# ascender_board.net
KiCad netlist of a schematic drawn in EAGLE
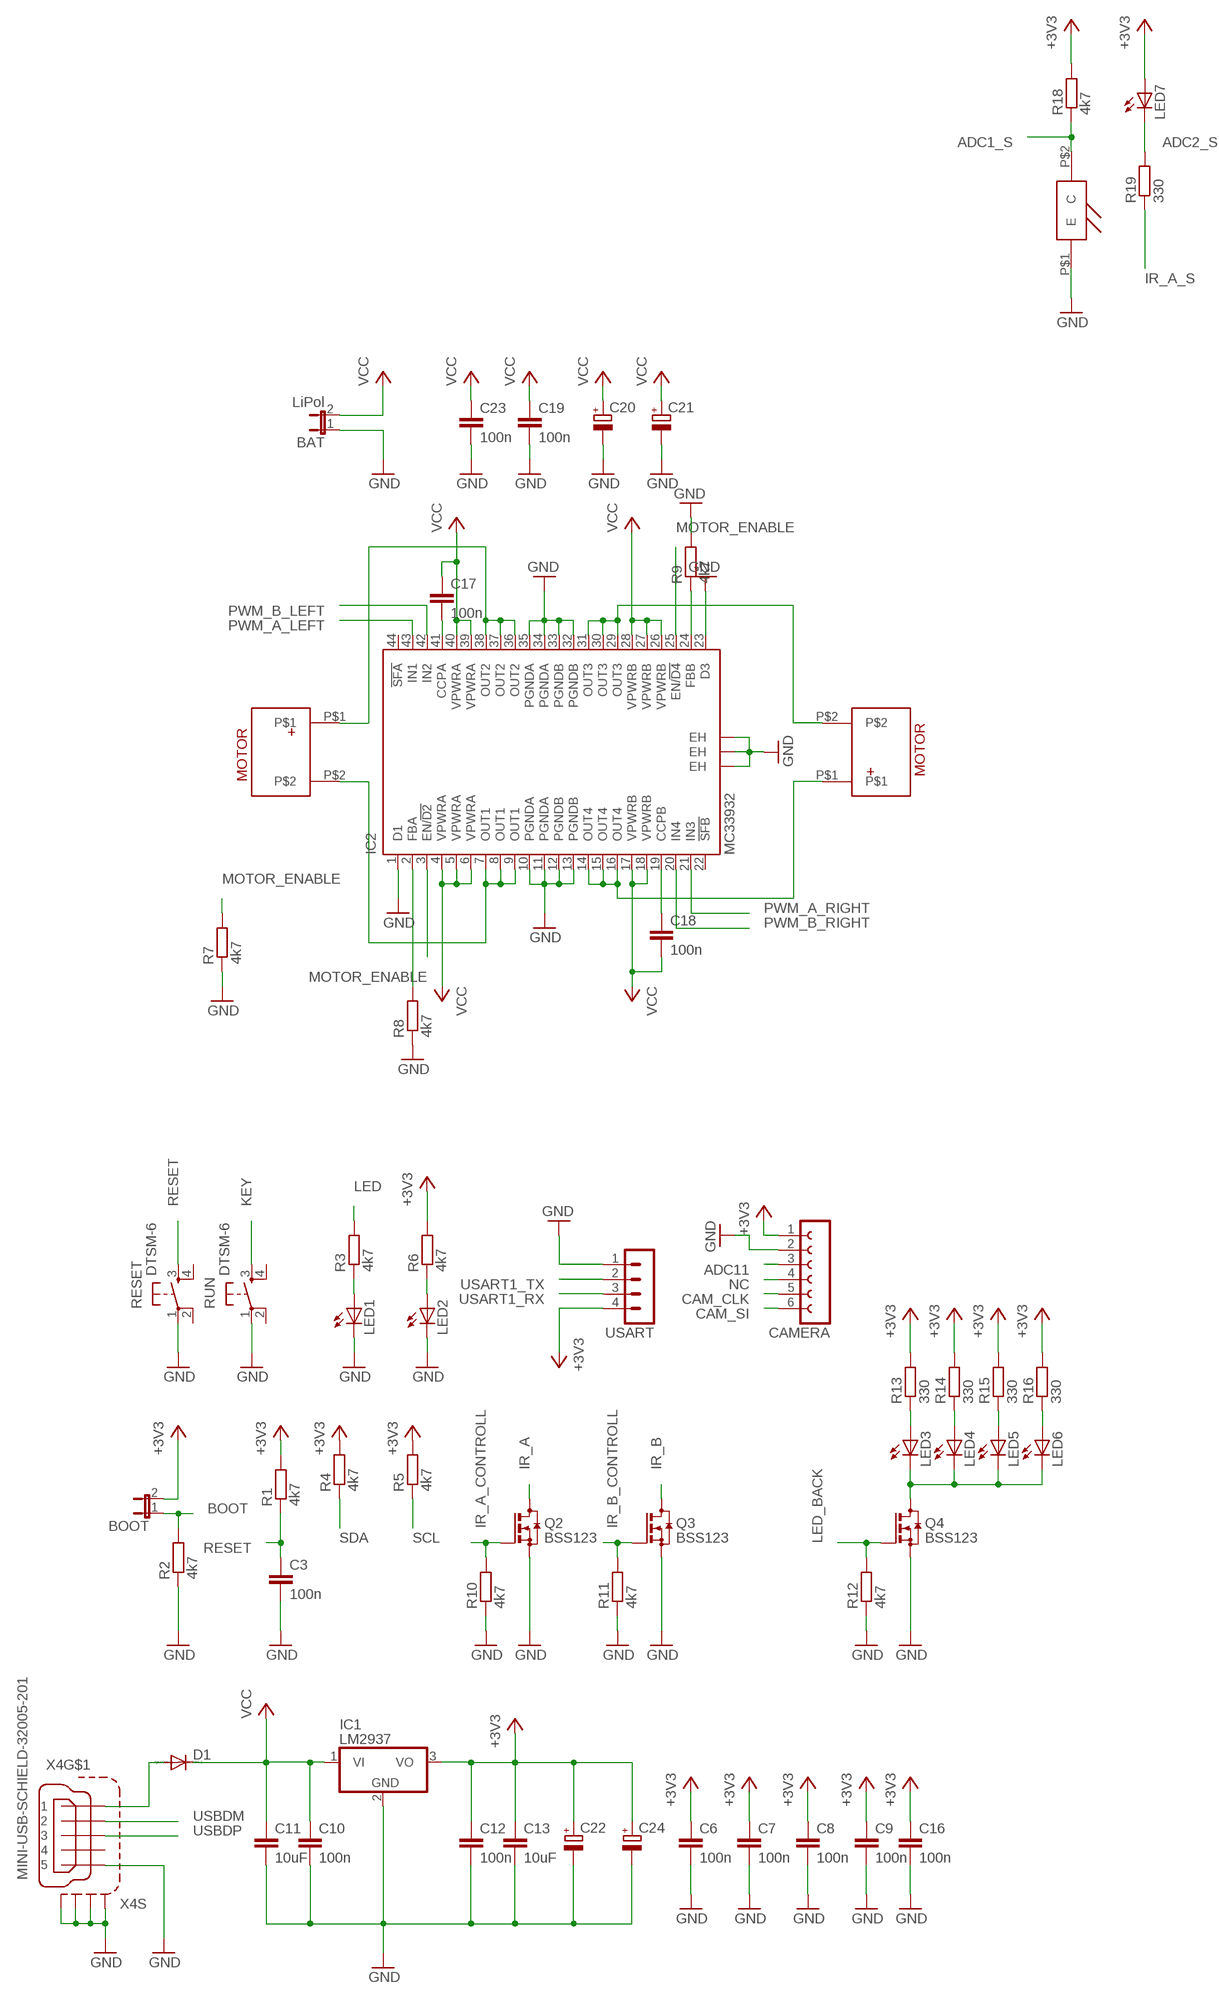
[diagram p0: schematic, sheet 1, part 1 of 2]
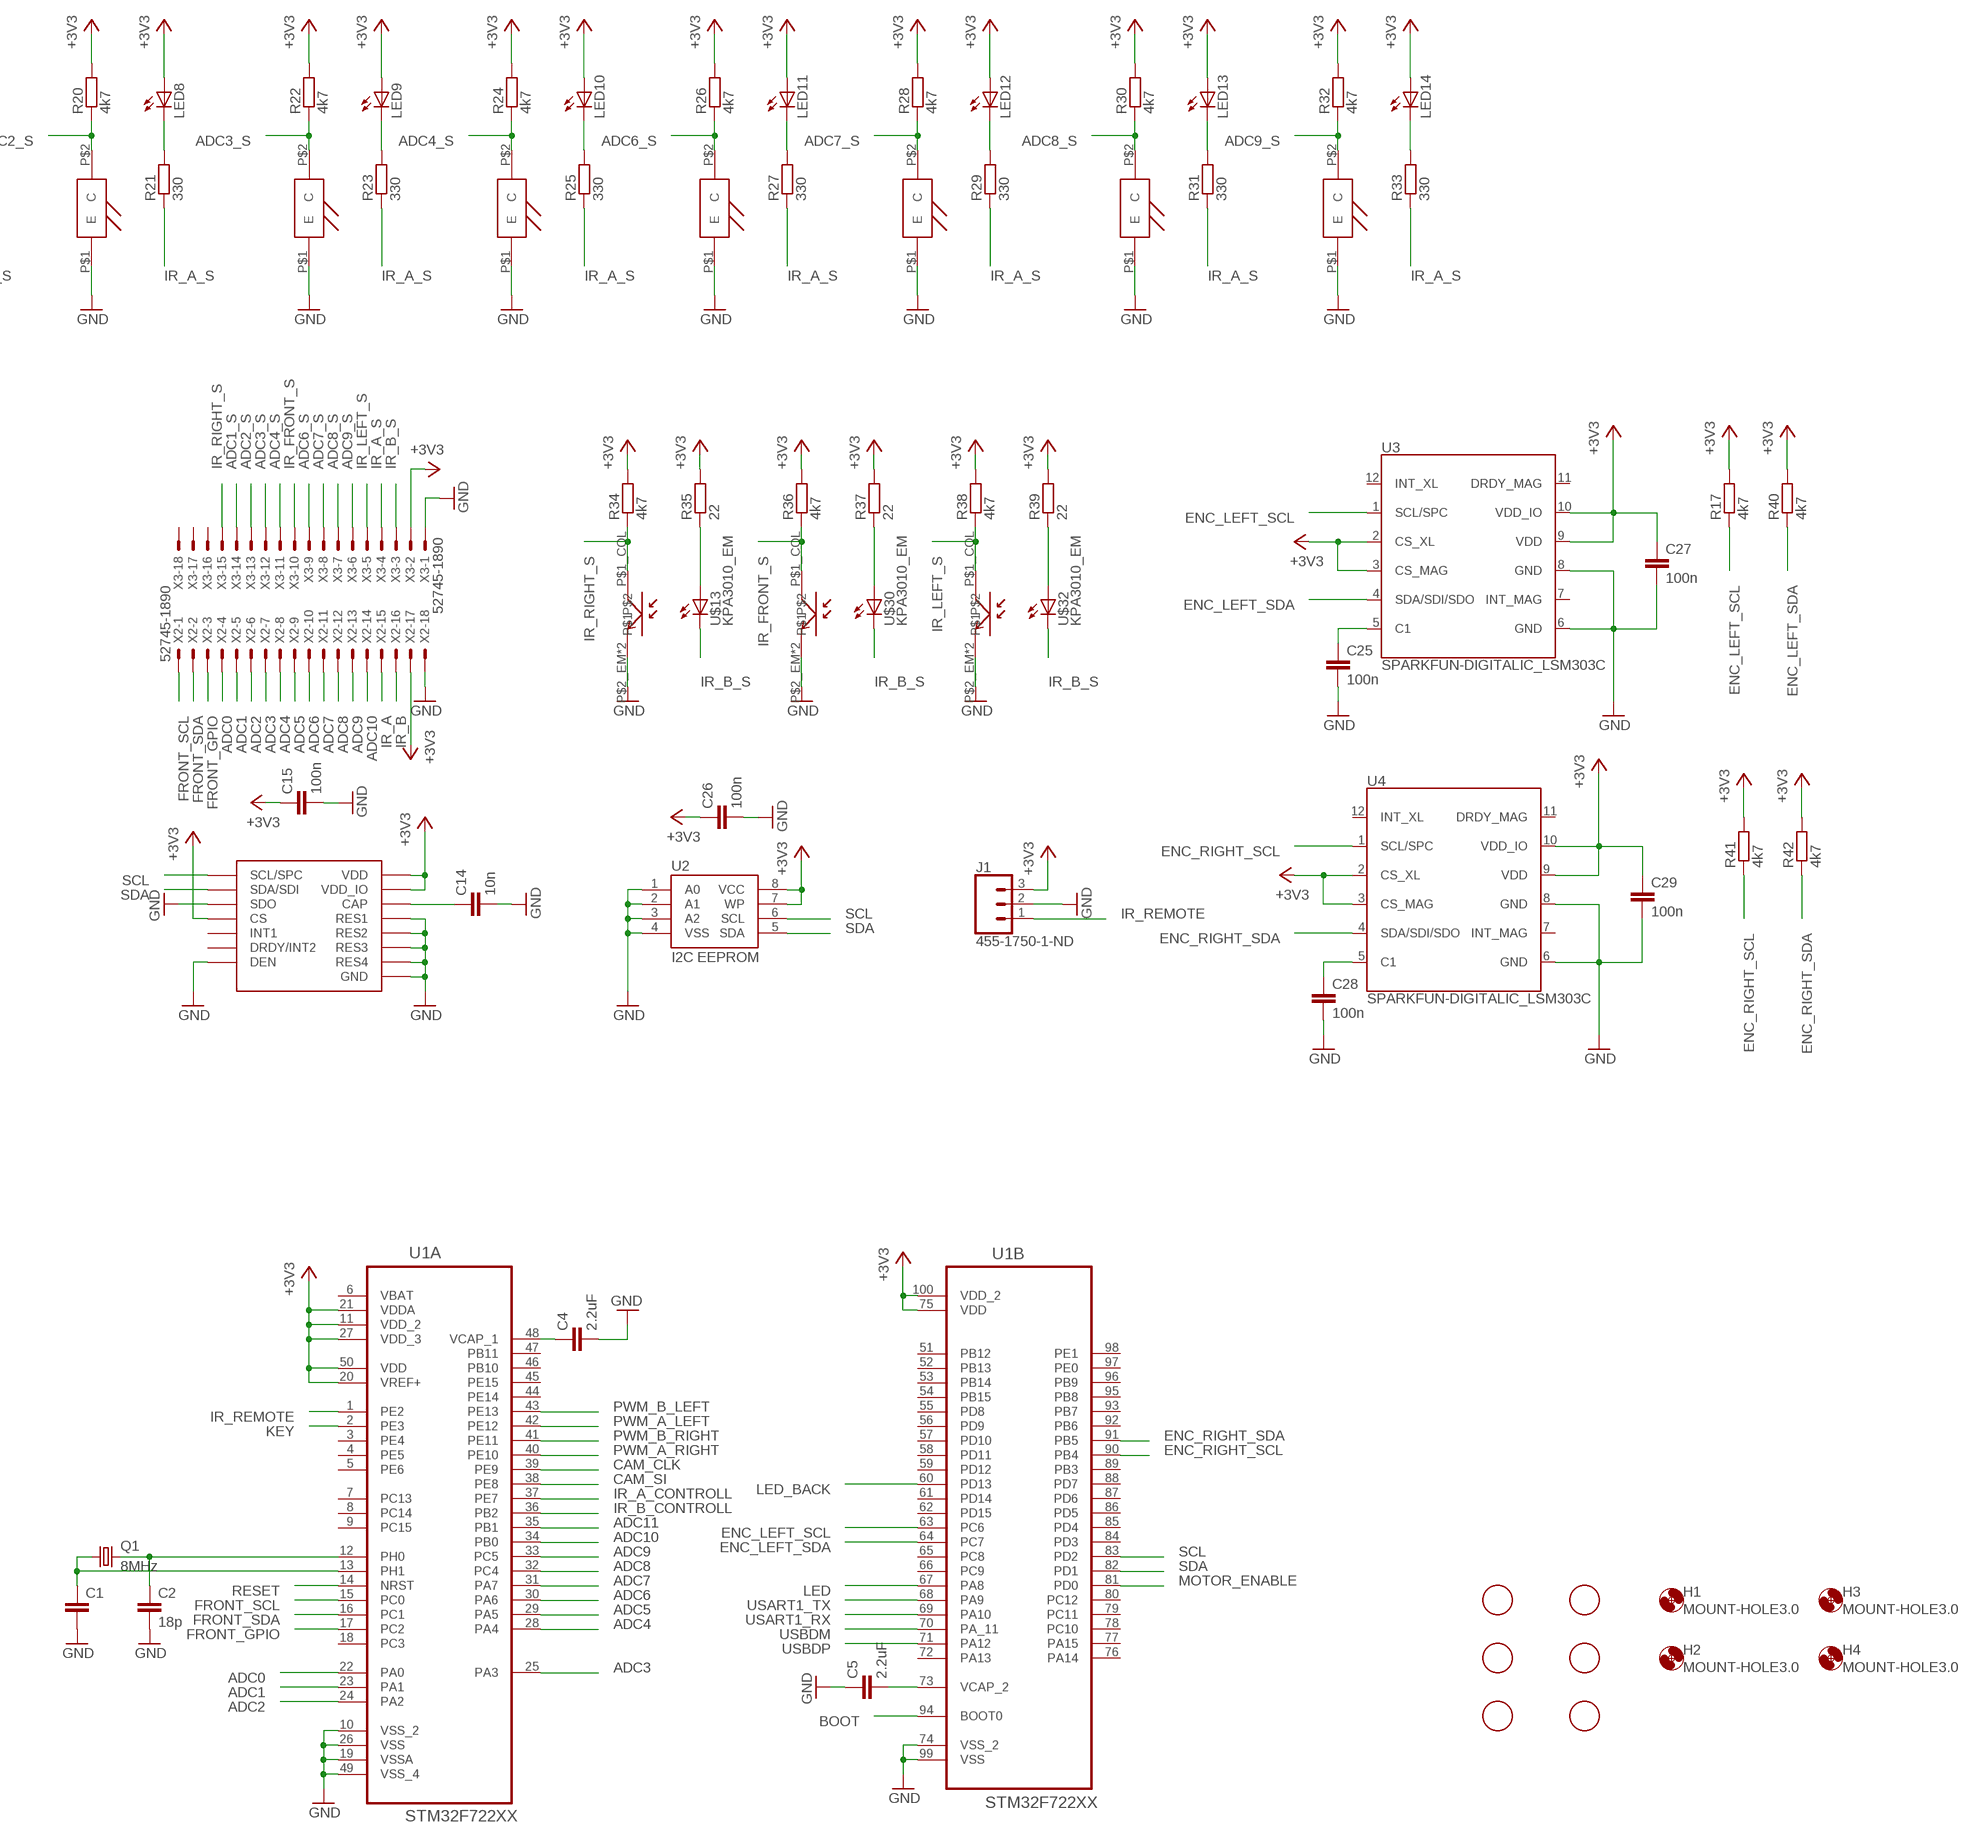
[diagram p1: schematic, sheet 1, part 2 of 2]

(export (version "E")
  (design (tool "Eeschema 10.0.6"))
  (components
    (comp (ref "BAT")
      (value "LiPol")
      (footprint "eagle-import:JP1")
      (libsource (lib "eagle-import") (part "JP1E"))
    )
    (comp (ref "BOOT")
      (value "JP1E")
      (footprint "eagle-import:JP1")
      (libsource (lib "eagle-import") (part "JP1E"))
    )
    (comp (ref "C1")
      (value "C-EUC0805")
      (footprint "eagle-import:C0805")
      (libsource (lib "eagle-import") (part "C-EUC0805"))
    )
    (comp (ref "C2")
      (value "18p")
      (footprint "eagle-import:C0805")
      (libsource (lib "eagle-import") (part "C-EUC0805"))
    )
    (comp (ref "C3")
      (value "100n")
      (footprint "eagle-import:C0805")
      (libsource (lib "eagle-import") (part "C-EUC0805"))
    )
    (comp (ref "C4")
      (value "2.2uF")
      (footprint "eagle-import:C0805")
      (libsource (lib "eagle-import") (part "C-EUC0805"))
    )
    (comp (ref "C5")
      (value "2.2uF")
      (footprint "eagle-import:C0805")
      (libsource (lib "eagle-import") (part "C-EUC0805"))
    )
    (comp (ref "C6")
      (value "100n")
      (footprint "eagle-import:C0805")
      (libsource (lib "eagle-import") (part "C-EUC0805"))
    )
    (comp (ref "C7")
      (value "100n")
      (footprint "eagle-import:C0805")
      (libsource (lib "eagle-import") (part "C-EUC0805"))
    )
    (comp (ref "C8")
      (value "100n")
      (footprint "eagle-import:C0805")
      (libsource (lib "eagle-import") (part "C-EUC0805"))
    )
    (comp (ref "C9")
      (value "100n")
      (footprint "eagle-import:C0805")
      (libsource (lib "eagle-import") (part "C-EUC0805"))
    )
    (comp (ref "C10")
      (value "100n")
      (footprint "eagle-import:C0805")
      (libsource (lib "eagle-import") (part "C-EUC0805"))
    )
    (comp (ref "C11")
      (value "10uF")
      (footprint "eagle-import:C0805")
      (libsource (lib "eagle-import") (part "C-EUC0805"))
    )
    (comp (ref "C12")
      (value "100n")
      (footprint "eagle-import:C0805")
      (libsource (lib "eagle-import") (part "C-EUC0805"))
    )
    (comp (ref "C13")
      (value "10uF")
      (footprint "eagle-import:C0805")
      (libsource (lib "eagle-import") (part "C-EUC0805"))
    )
    (comp (ref "C14")
      (value "10n")
      (footprint "eagle-import:C0805")
      (libsource (lib "eagle-import") (part "C-EUC0805"))
    )
    (comp (ref "C15")
      (value "100n")
      (footprint "eagle-import:C0805")
      (libsource (lib "eagle-import") (part "C-EUC0805"))
    )
    (comp (ref "C16")
      (value "100n")
      (footprint "eagle-import:C0805")
      (libsource (lib "eagle-import") (part "C-EUC0805"))
    )
    (comp (ref "C17")
      (value "100n")
      (footprint "eagle-import:C0805")
      (libsource (lib "eagle-import") (part "C-EUC0805"))
    )
    (comp (ref "C18")
      (value "100n")
      (footprint "eagle-import:C0805")
      (libsource (lib "eagle-import") (part "C-EUC0805"))
    )
    (comp (ref "C19")
      (value "100n")
      (footprint "eagle-import:C0805")
      (libsource (lib "eagle-import") (part "C-EUC0805"))
    )
    (comp (ref "C20")
      (value "CPOL-EU153CLV-0505")
      (footprint "eagle-import:153CLV-0505")
      (libsource (lib "eagle-import") (part "CPOL-EU153CLV-0505"))
    )
    (comp (ref "C21")
      (value "CPOL-EU153CLV-0505")
      (footprint "eagle-import:153CLV-0505")
      (libsource (lib "eagle-import") (part "CPOL-EU153CLV-0505"))
    )
    (comp (ref "C22")
      (value "CPOL-EU153CLV-0505")
      (footprint "eagle-import:153CLV-0505")
      (libsource (lib "eagle-import") (part "CPOL-EU153CLV-0505"))
    )
    (comp (ref "C23")
      (value "100n")
      (footprint "eagle-import:C0805")
      (libsource (lib "eagle-import") (part "C-EUC0805"))
    )
    (comp (ref "C24")
      (value "CPOL-EU153CLV-0505")
      (footprint "eagle-import:153CLV-0505")
      (libsource (lib "eagle-import") (part "CPOL-EU153CLV-0505"))
    )
    (comp (ref "C25")
      (value "100n")
      (footprint "eagle-import:C0805")
      (libsource (lib "eagle-import") (part "C-EUC0805"))
    )
    (comp (ref "C26")
      (value "100n")
      (footprint "eagle-import:C0805")
      (libsource (lib "eagle-import") (part "C-EUC0805"))
    )
    (comp (ref "C27")
      (value "100n")
      (footprint "eagle-import:C0805")
      (libsource (lib "eagle-import") (part "C-EUC0805"))
    )
    (comp (ref "C28")
      (value "100n")
      (footprint "eagle-import:C0805")
      (libsource (lib "eagle-import") (part "C-EUC0805"))
    )
    (comp (ref "C29")
      (value "100n")
      (footprint "eagle-import:C0805")
      (libsource (lib "eagle-import") (part "C-EUC0805"))
    )
    (comp (ref "CAMERA")
      (value "FE06-1")
      (footprint "eagle-import:FE06")
      (libsource (lib "eagle-import") (part "FE06-1"))
    )
    (comp (ref "D1")
      (value "DIODE-DO-214AC")
      (footprint "eagle-import:DO-214AC")
      (libsource (lib "eagle-import") (part "DIODE-DO-214AC"))
    )
    (comp (ref "H1")
      (value "MOUNT-HOLE3.0")
      (footprint "eagle-import:3,0")
      (libsource (lib "eagle-import") (part "MOUNT-HOLE3.0"))
    )
    (comp (ref "H2")
      (value "MOUNT-HOLE3.0")
      (footprint "eagle-import:3,0")
      (libsource (lib "eagle-import") (part "MOUNT-HOLE3.0"))
    )
    (comp (ref "H3")
      (value "MOUNT-HOLE3.0")
      (footprint "eagle-import:3,0")
      (libsource (lib "eagle-import") (part "MOUNT-HOLE3.0"))
    )
    (comp (ref "H4")
      (value "MOUNT-HOLE3.0")
      (footprint "eagle-import:3,0")
      (libsource (lib "eagle-import") (part "MOUNT-HOLE3.0"))
    )
    (comp (ref "IC1")
      (value "LM2937")
      (footprint "eagle-import:TO263-3")
      (libsource (lib "eagle-import") (part "LM2937"))
    )
    (comp (ref "IC2")
      (value "MC33932")
      (footprint "eagle-import:HSOP44")
      (fields (field (name "MPN") "MC33932VW"))
      (libsource (lib "eagle-import") (part "MC33932"))
    )
    (comp (ref "J1")
      (value "455-1750-1-ND")
      (footprint "eagle-import:1X03")
      (libsource (lib "eagle-import") (part "CONN_03"))
    )
    (comp (ref "LED1")
      (value "LEDCHIPLED_1206")
      (footprint "eagle-import:CHIPLED_1206")
      (libsource (lib "eagle-import") (part "LEDCHIPLED_1206"))
    )
    (comp (ref "LED2")
      (value "LEDCHIPLED_1206")
      (footprint "eagle-import:CHIPLED_1206")
      (libsource (lib "eagle-import") (part "LEDCHIPLED_1206"))
    )
    (comp (ref "LED3")
      (value "LEDCHIPLED_1206")
      (footprint "eagle-import:CHIPLED_1206")
      (libsource (lib "eagle-import") (part "LEDCHIPLED_1206"))
    )
    (comp (ref "LED4")
      (value "LEDCHIPLED_1206")
      (footprint "eagle-import:CHIPLED_1206")
      (libsource (lib "eagle-import") (part "LEDCHIPLED_1206"))
    )
    (comp (ref "LED5")
      (value "LEDCHIPLED_1206")
      (footprint "eagle-import:CHIPLED_1206")
      (libsource (lib "eagle-import") (part "LEDCHIPLED_1206"))
    )
    (comp (ref "LED6")
      (value "LEDCHIPLED_1206")
      (footprint "eagle-import:CHIPLED_1206")
      (libsource (lib "eagle-import") (part "LEDCHIPLED_1206"))
    )
    (comp (ref "LED7")
      (value "LEDCHIPLED_1206")
      (footprint "eagle-import:CHIPLED_1206")
      (libsource (lib "eagle-import") (part "LEDCHIPLED_1206"))
    )
    (comp (ref "LED8")
      (value "LEDCHIPLED_1206")
      (footprint "eagle-import:CHIPLED_1206")
      (libsource (lib "eagle-import") (part "LEDCHIPLED_1206"))
    )
    (comp (ref "LED9")
      (value "LEDCHIPLED_1206")
      (footprint "eagle-import:CHIPLED_1206")
      (libsource (lib "eagle-import") (part "LEDCHIPLED_1206"))
    )
    (comp (ref "LED10")
      (value "LEDCHIPLED_1206")
      (footprint "eagle-import:CHIPLED_1206")
      (libsource (lib "eagle-import") (part "LEDCHIPLED_1206"))
    )
    (comp (ref "LED11")
      (value "LEDCHIPLED_1206")
      (footprint "eagle-import:CHIPLED_1206")
      (libsource (lib "eagle-import") (part "LEDCHIPLED_1206"))
    )
    (comp (ref "LED12")
      (value "LEDCHIPLED_1206")
      (footprint "eagle-import:CHIPLED_1206")
      (libsource (lib "eagle-import") (part "LEDCHIPLED_1206"))
    )
    (comp (ref "LED13")
      (value "LEDCHIPLED_1206")
      (footprint "eagle-import:CHIPLED_1206")
      (libsource (lib "eagle-import") (part "LEDCHIPLED_1206"))
    )
    (comp (ref "LED14")
      (value "LEDCHIPLED_1206")
      (footprint "eagle-import:CHIPLED_1206")
      (libsource (lib "eagle-import") (part "LEDCHIPLED_1206"))
    )
    (comp (ref "Q1")
      (value "8MHz")
      (footprint "eagle-import:CTS406")
      (libsource (lib "eagle-import") (part "CRYSTALCTS406"))
    )
    (comp (ref "Q2")
      (value "BSS123")
      (footprint "eagle-import:SOT23")
      (libsource (lib "eagle-import") (part "BSS123"))
    )
    (comp (ref "Q3")
      (value "BSS123")
      (footprint "eagle-import:SOT23")
      (libsource (lib "eagle-import") (part "BSS123"))
    )
    (comp (ref "Q4")
      (value "BSS123")
      (footprint "eagle-import:SOT23")
      (libsource (lib "eagle-import") (part "BSS123"))
    )
    (comp (ref "R1")
      (value "4k7")
      (footprint "eagle-import:M0805")
      (libsource (lib "eagle-import") (part "R-EU_M0805"))
    )
    (comp (ref "R2")
      (value "4k7")
      (footprint "eagle-import:M0805")
      (libsource (lib "eagle-import") (part "R-EU_M0805"))
    )
    (comp (ref "R3")
      (value "4k7")
      (footprint "eagle-import:M0805")
      (libsource (lib "eagle-import") (part "R-EU_M0805"))
    )
    (comp (ref "R4")
      (value "4k7")
      (footprint "eagle-import:M0805")
      (libsource (lib "eagle-import") (part "R-EU_M0805"))
    )
    (comp (ref "R5")
      (value "4k7")
      (footprint "eagle-import:M0805")
      (libsource (lib "eagle-import") (part "R-EU_M0805"))
    )
    (comp (ref "R6")
      (value "4k7")
      (footprint "eagle-import:M0805")
      (libsource (lib "eagle-import") (part "R-EU_M0805"))
    )
    (comp (ref "R7")
      (value "4k7")
      (footprint "eagle-import:M0805")
      (libsource (lib "eagle-import") (part "R-EU_M0805"))
    )
    (comp (ref "R8")
      (value "4k7")
      (footprint "eagle-import:M0805")
      (libsource (lib "eagle-import") (part "R-EU_M0805"))
    )
    (comp (ref "R9")
      (value "4k7")
      (footprint "eagle-import:M0805")
      (libsource (lib "eagle-import") (part "R-EU_M0805"))
    )
    (comp (ref "R10")
      (value "4k7")
      (footprint "eagle-import:M0805")
      (libsource (lib "eagle-import") (part "R-EU_M0805"))
    )
    (comp (ref "R11")
      (value "4k7")
      (footprint "eagle-import:M0805")
      (libsource (lib "eagle-import") (part "R-EU_M0805"))
    )
    (comp (ref "R12")
      (value "4k7")
      (footprint "eagle-import:M0805")
      (libsource (lib "eagle-import") (part "R-EU_M0805"))
    )
    (comp (ref "R13")
      (value "330")
      (footprint "eagle-import:M0805")
      (libsource (lib "eagle-import") (part "R-EU_M0805"))
    )
    (comp (ref "R14")
      (value "330")
      (footprint "eagle-import:M0805")
      (libsource (lib "eagle-import") (part "R-EU_M0805"))
    )
    (comp (ref "R15")
      (value "330")
      (footprint "eagle-import:M0805")
      (libsource (lib "eagle-import") (part "R-EU_M0805"))
    )
    (comp (ref "R16")
      (value "330")
      (footprint "eagle-import:M0805")
      (libsource (lib "eagle-import") (part "R-EU_M0805"))
    )
    (comp (ref "R17")
      (value "4k7")
      (footprint "eagle-import:M0805")
      (libsource (lib "eagle-import") (part "R-EU_M0805"))
    )
    (comp (ref "R18")
      (value "4k7")
      (footprint "eagle-import:M0805")
      (libsource (lib "eagle-import") (part "R-EU_M0805"))
    )
    (comp (ref "R19")
      (value "330")
      (footprint "eagle-import:M0805")
      (libsource (lib "eagle-import") (part "R-EU_M0805"))
    )
    (comp (ref "R20")
      (value "4k7")
      (footprint "eagle-import:M0805")
      (libsource (lib "eagle-import") (part "R-EU_M0805"))
    )
    (comp (ref "R21")
      (value "330")
      (footprint "eagle-import:M0805")
      (libsource (lib "eagle-import") (part "R-EU_M0805"))
    )
    (comp (ref "R22")
      (value "4k7")
      (footprint "eagle-import:M0805")
      (libsource (lib "eagle-import") (part "R-EU_M0805"))
    )
    (comp (ref "R23")
      (value "330")
      (footprint "eagle-import:M0805")
      (libsource (lib "eagle-import") (part "R-EU_M0805"))
    )
    (comp (ref "R24")
      (value "4k7")
      (footprint "eagle-import:M0805")
      (libsource (lib "eagle-import") (part "R-EU_M0805"))
    )
    (comp (ref "R25")
      (value "330")
      (footprint "eagle-import:M0805")
      (libsource (lib "eagle-import") (part "R-EU_M0805"))
    )
    (comp (ref "R26")
      (value "4k7")
      (footprint "eagle-import:M0805")
      (libsource (lib "eagle-import") (part "R-EU_M0805"))
    )
    (comp (ref "R27")
      (value "330")
      (footprint "eagle-import:M0805")
      (libsource (lib "eagle-import") (part "R-EU_M0805"))
    )
    (comp (ref "R28")
      (value "4k7")
      (footprint "eagle-import:M0805")
      (libsource (lib "eagle-import") (part "R-EU_M0805"))
    )
    (comp (ref "R29")
      (value "330")
      (footprint "eagle-import:M0805")
      (libsource (lib "eagle-import") (part "R-EU_M0805"))
    )
    (comp (ref "R30")
      (value "4k7")
      (footprint "eagle-import:M0805")
      (libsource (lib "eagle-import") (part "R-EU_M0805"))
    )
    (comp (ref "R31")
      (value "330")
      (footprint "eagle-import:M0805")
      (libsource (lib "eagle-import") (part "R-EU_M0805"))
    )
    (comp (ref "R32")
      (value "4k7")
      (footprint "eagle-import:M0805")
      (libsource (lib "eagle-import") (part "R-EU_M0805"))
    )
    (comp (ref "R33")
      (value "330")
      (footprint "eagle-import:M0805")
      (libsource (lib "eagle-import") (part "R-EU_M0805"))
    )
    (comp (ref "R34")
      (value "4k7")
      (footprint "eagle-import:M0805")
      (libsource (lib "eagle-import") (part "R-EU_M0805"))
    )
    (comp (ref "R35")
      (value "22")
      (footprint "eagle-import:M0805")
      (libsource (lib "eagle-import") (part "R-EU_M0805"))
    )
    (comp (ref "R36")
      (value "4k7")
      (footprint "eagle-import:M0805")
      (libsource (lib "eagle-import") (part "R-EU_M0805"))
    )
    (comp (ref "R37")
      (value "22")
      (footprint "eagle-import:M0805")
      (libsource (lib "eagle-import") (part "R-EU_M0805"))
    )
    (comp (ref "R38")
      (value "4k7")
      (footprint "eagle-import:M0805")
      (libsource (lib "eagle-import") (part "R-EU_M0805"))
    )
    (comp (ref "R39")
      (value "22")
      (footprint "eagle-import:M0805")
      (libsource (lib "eagle-import") (part "R-EU_M0805"))
    )
    (comp (ref "R40")
      (value "4k7")
      (footprint "eagle-import:M0805")
      (libsource (lib "eagle-import") (part "R-EU_M0805"))
    )
    (comp (ref "R41")
      (value "4k7")
      (footprint "eagle-import:M0805")
      (libsource (lib "eagle-import") (part "R-EU_M0805"))
    )
    (comp (ref "R42")
      (value "4k7")
      (footprint "eagle-import:M0805")
      (libsource (lib "eagle-import") (part "R-EU_M0805"))
    )
    (comp (ref "RESET")
      (value "DTSM-6")
      (footprint "eagle-import:DTSM-6")
      (libsource (lib "eagle-import") (part "DTSM-6"))
    )
    (comp (ref "RUN")
      (value "DTSM-6")
      (footprint "eagle-import:DTSM-6")
      (libsource (lib "eagle-import") (part "DTSM-6"))
    )
    (comp (ref "U$2")
      (value "ST_L3GD20H")
      (footprint "eagle-import:ST_LGA16L")
      (libsource (lib "eagle-import") (part "ST_L3GD20H"))
    )
    (comp (ref "U$3")
      (value "FIDUCIAL")
      (footprint "eagle-import:FIDUCIAL_1MM")
      (libsource (lib "eagle-import") (part "FIDUCIAL"))
    )
    (comp (ref "U$4")
      (value "FIDUCIAL")
      (footprint "eagle-import:FIDUCIAL_1MM")
      (libsource (lib "eagle-import") (part "FIDUCIAL"))
    )
    (comp (ref "U$5")
      (value "FIDUCIAL")
      (footprint "eagle-import:FIDUCIAL_1MM")
      (libsource (lib "eagle-import") (part "FIDUCIAL"))
    )
    (comp (ref "U$6")
      (value "FIDUCIAL")
      (footprint "eagle-import:FIDUCIAL_1MM")
      (libsource (lib "eagle-import") (part "FIDUCIAL"))
    )
    (comp (ref "U$7")
      (value "FIDUCIAL")
      (footprint "eagle-import:FIDUCIAL_1MM")
      (libsource (lib "eagle-import") (part "FIDUCIAL"))
    )
    (comp (ref "U$8")
      (value "FIDUCIAL")
      (footprint "eagle-import:FIDUCIAL_1MM")
      (libsource (lib "eagle-import") (part "FIDUCIAL"))
    )
    (comp (ref "U$11")
      (value "SFH3710")
      (footprint "eagle-import:SFH3710")
      (libsource (lib "eagle-import") (part "SFH3710"))
    )
    (comp (ref "U$12")
      (value "KPA3010")
      (footprint "eagle-import:KPA3010")
      (libsource (lib "eagle-import") (part "KPA3010"))
    )
    (comp (ref "U$13")
      (value "KPA3010_EM")
      (footprint "eagle-import:KPA3010")
      (libsource (lib "eagle-import") (part "KPA3010_EM"))
    )
    (comp (ref "U$14")
      (value "SFH3710")
      (footprint "eagle-import:SFH3710")
      (libsource (lib "eagle-import") (part "SFH3710"))
    )
    (comp (ref "U$15")
      (value "SFH3710")
      (footprint "eagle-import:SFH3710")
      (libsource (lib "eagle-import") (part "SFH3710"))
    )
    (comp (ref "U$16")
      (value "SFH3710")
      (footprint "eagle-import:SFH3710")
      (libsource (lib "eagle-import") (part "SFH3710"))
    )
    (comp (ref "U$17")
      (value "SFH3710")
      (footprint "eagle-import:SFH3710")
      (libsource (lib "eagle-import") (part "SFH3710"))
    )
    (comp (ref "U$18")
      (value "SFH3710")
      (footprint "eagle-import:SFH3710")
      (libsource (lib "eagle-import") (part "SFH3710"))
    )
    (comp (ref "U$19")
      (value "SFH3710")
      (footprint "eagle-import:SFH3710")
      (libsource (lib "eagle-import") (part "SFH3710"))
    )
    (comp (ref "U$20")
      (value "SFH3710")
      (footprint "eagle-import:SFH3710")
      (libsource (lib "eagle-import") (part "SFH3710"))
    )
    (comp (ref "U$26")
      (value "JSUMO_MOTOR_WITH_WHEEL")
      (footprint "eagle-import:JSUMO_MOTOR_WITH_WHEEL")
      (libsource (lib "eagle-import") (part "JSUMO_MOTOR_WITH_WHEEL"))
    )
    (comp (ref "U$27")
      (value "JSUMO_MOTOR_WITH_WHEEL")
      (footprint "eagle-import:JSUMO_MOTOR_WITH_WHEEL")
      (libsource (lib "eagle-import") (part "JSUMO_MOTOR_WITH_WHEEL"))
    )
    (comp (ref "U$29")
      (value "KPA3010")
      (footprint "eagle-import:KPA3010")
      (libsource (lib "eagle-import") (part "KPA3010"))
    )
    (comp (ref "U$30")
      (value "KPA3010_EM")
      (footprint "eagle-import:KPA3010")
      (libsource (lib "eagle-import") (part "KPA3010_EM"))
    )
    (comp (ref "U$31")
      (value "KPA3010")
      (footprint "eagle-import:KPA3010")
      (libsource (lib "eagle-import") (part "KPA3010"))
    )
    (comp (ref "U$32")
      (value "KPA3010_EM")
      (footprint "eagle-import:KPA3010")
      (libsource (lib "eagle-import") (part "KPA3010_EM"))
    )
    (comp (ref "U1")
      (value "STM32F722XX")
      (footprint "eagle-import:QFP50P1600X1600X160-100N")
      (fields (field (name "MPN") "STM32F407VET6"))
      (libsource (lib "eagle-import") (part "STM32F722XX"))
    )
    (comp (ref "U2")
      (value "I2C EEPROM")
      (footprint "eagle-import:SO08-EIAJ")
      (libsource (lib "eagle-import") (part "EEPROM-I2CEIAJ"))
    )
    (comp (ref "U3")
      (value "SPARKFUN-DIGITALIC_LSM303C")
      (footprint "eagle-import:SPARKFUN-DIGITALIC_LGA-12")
      (libsource (lib "eagle-import") (part "SPARKFUN-DIGITALIC_LSM303C"))
    )
    (comp (ref "U4")
      (value "SPARKFUN-DIGITALIC_LSM303C")
      (footprint "eagle-import:SPARKFUN-DIGITALIC_LGA-12")
      (libsource (lib "eagle-import") (part "SPARKFUN-DIGITALIC_LSM303C"))
    )
    (comp (ref "USART")
      (value "MA04-1")
      (footprint "eagle-import:MA04-1")
      (libsource (lib "eagle-import") (part "MA04-1"))
    )
    (comp (ref "X2")
      (value "52745-1890")
      (footprint "eagle-import:52745-1890")
      (fields (field (name "MF") "MOLEX"))
      (libsource (lib "eagle-import") (part "52745-1890"))
    )
    (comp (ref "X3")
      (value "52745-1890")
      (footprint "eagle-import:52745-1890")
      (fields (field (name "MF") "MOLEX"))
      (libsource (lib "eagle-import") (part "52745-1890"))
    )
    (comp (ref "X4")
      (value "MINI-USB-SCHIELD-32005-201")
      (footprint "eagle-import:32005-201")
      (libsource (lib "eagle-import") (part "MINI-USB-SCHIELD-32005-201"))
    )
  )
  (nets
    (net (code "1") (name "+3V3") (class "Default")
      (node (ref "BOOT") (pin "2") (pinfunction "2_2") (pintype "passive"))
      (node (ref "C12") (pin "1") (pinfunction "1_1") (pintype "passive"))
      (node (ref "C13") (pin "1") (pinfunction "1_1") (pintype "passive"))
      (node (ref "C15") (pin "1") (pinfunction "1_1") (pintype "passive"))
      (node (ref "C16") (pin "1") (pinfunction "1_1") (pintype "passive"))
      (node (ref "C22") (pin "+") (pinfunction "+_+") (pintype "passive"))
      (node (ref "C24") (pin "+") (pinfunction "+_+") (pintype "passive"))
      (node (ref "C26") (pin "1") (pinfunction "1_1") (pintype "passive"))
      (node (ref "C27") (pin "1") (pinfunction "1_1") (pintype "passive"))
      (node (ref "C29") (pin "1") (pinfunction "1_1") (pintype "passive"))
      (node (ref "C6") (pin "1") (pinfunction "1_1") (pintype "passive"))
      (node (ref "C7") (pin "1") (pinfunction "1_1") (pintype "passive"))
      (node (ref "C8") (pin "1") (pinfunction "1_1") (pintype "passive"))
      (node (ref "C9") (pin "1") (pinfunction "1_1") (pintype "passive"))
      (node (ref "CAMERA") (pin "1") (pinfunction "1_1") (pintype "passive"))
      (node (ref "IC1") (pin "3") (pinfunction "VO_3") (pintype "passive"))
      (node (ref "J1") (pin "3") (pinfunction "3_3") (pintype "passive"))
      (node (ref "LED10") (pin "A") (pinfunction "A_A") (pintype "passive"))
      (node (ref "LED11") (pin "A") (pinfunction "A_A") (pintype "passive"))
      (node (ref "LED12") (pin "A") (pinfunction "A_A") (pintype "passive"))
      (node (ref "LED13") (pin "A") (pinfunction "A_A") (pintype "passive"))
      (node (ref "LED14") (pin "A") (pinfunction "A_A") (pintype "passive"))
      (node (ref "LED7") (pin "A") (pinfunction "A_A") (pintype "passive"))
      (node (ref "LED8") (pin "A") (pinfunction "A_A") (pintype "passive"))
      (node (ref "LED9") (pin "A") (pinfunction "A_A") (pintype "passive"))
      (node (ref "R1") (pin "2") (pinfunction "2_2") (pintype "passive"))
      (node (ref "R13") (pin "2") (pinfunction "2_2") (pintype "passive"))
      (node (ref "R14") (pin "2") (pinfunction "2_2") (pintype "passive"))
      (node (ref "R15") (pin "2") (pinfunction "2_2") (pintype "passive"))
      (node (ref "R16") (pin "2") (pinfunction "2_2") (pintype "passive"))
      (node (ref "R17") (pin "2") (pinfunction "2_2") (pintype "passive"))
      (node (ref "R18") (pin "2") (pinfunction "2_2") (pintype "passive"))
      (node (ref "R20") (pin "2") (pinfunction "2_2") (pintype "passive"))
      (node (ref "R22") (pin "2") (pinfunction "2_2") (pintype "passive"))
      (node (ref "R24") (pin "2") (pinfunction "2_2") (pintype "passive"))
      (node (ref "R26") (pin "2") (pinfunction "2_2") (pintype "passive"))
      (node (ref "R28") (pin "2") (pinfunction "2_2") (pintype "passive"))
      (node (ref "R30") (pin "2") (pinfunction "2_2") (pintype "passive"))
      (node (ref "R32") (pin "2") (pinfunction "2_2") (pintype "passive"))
      (node (ref "R34") (pin "2") (pinfunction "2_2") (pintype "passive"))
      (node (ref "R35") (pin "2") (pinfunction "2_2") (pintype "passive"))
      (node (ref "R36") (pin "2") (pinfunction "2_2") (pintype "passive"))
      (node (ref "R37") (pin "2") (pinfunction "2_2") (pintype "passive"))
      (node (ref "R38") (pin "2") (pinfunction "2_2") (pintype "passive"))
      (node (ref "R39") (pin "2") (pinfunction "2_2") (pintype "passive"))
      (node (ref "R4") (pin "2") (pinfunction "2_2") (pintype "passive"))
      (node (ref "R40") (pin "2") (pinfunction "2_2") (pintype "passive"))
      (node (ref "R41") (pin "2") (pinfunction "2_2") (pintype "passive"))
      (node (ref "R42") (pin "2") (pinfunction "2_2") (pintype "passive"))
      (node (ref "R5") (pin "2") (pinfunction "2_2") (pintype "passive"))
      (node (ref "R6") (pin "2") (pinfunction "2_2") (pintype "passive"))
      (node (ref "U$2") (pin "P$1") (pinfunction "VDD_IO_P$1") (pintype "power_in"))
      (node (ref "U$2") (pin "P$16") (pinfunction "VDD_P$16") (pintype "power_in"))
      (node (ref "U$2") (pin "P$5") (pinfunction "CS_P$5") (pintype "bidirectional"))
      (node (ref "U1") (pin "100") (pinfunction "VDD_2_100") (pintype "power_in"))
      (node (ref "U1") (pin "11") (pinfunction "VDD_2_11") (pintype "power_in"))
      (node (ref "U1") (pin "20") (pinfunction "VREF+_20") (pintype "power_in"))
      (node (ref "U1") (pin "21") (pinfunction "VDDA_21") (pintype "power_in"))
      (node (ref "U1") (pin "27") (pinfunction "VDD_3_27") (pintype "power_in"))
      (node (ref "U1") (pin "50") (pinfunction "VDD_50") (pintype "power_in"))
      (node (ref "U1") (pin "75") (pinfunction "VDD_75") (pintype "power_in"))
      (node (ref "U2") (pin "7") (pinfunction "WP_7") (pintype "bidirectional"))
      (node (ref "U2") (pin "8") (pinfunction "VCC_8") (pintype "power_in"))
      (node (ref "U3") (pin "10") (pinfunction "VDD_IO_10") (pintype "bidirectional"))
      (node (ref "U3") (pin "2") (pinfunction "CS_XL_2") (pintype "bidirectional"))
      (node (ref "U3") (pin "3") (pinfunction "CS_MAG_3") (pintype "bidirectional"))
      (node (ref "U3") (pin "9") (pinfunction "VDD_9") (pintype "bidirectional"))
      (node (ref "U4") (pin "10") (pinfunction "VDD_IO_10") (pintype "bidirectional"))
      (node (ref "U4") (pin "2") (pinfunction "CS_XL_2") (pintype "bidirectional"))
      (node (ref "U4") (pin "3") (pinfunction "CS_MAG_3") (pintype "bidirectional"))
      (node (ref "U4") (pin "9") (pinfunction "VDD_9") (pintype "bidirectional"))
      (node (ref "USART") (pin "4") (pinfunction "4_4") (pintype "passive"))
      (node (ref "X2") (pin "17") (pinfunction "S_17") (pintype "passive"))
      (node (ref "X3") (pin "2") (pinfunction "S_2") (pintype "passive"))
    )
    (net (code "2") (name "/ADC0") (class "Default")
      (node (ref "U1") (pin "22") (pinfunction "PA0_22") (pintype "bidirectional"))
      (node (ref "X2") (pin "4") (pinfunction "S_4") (pintype "passive"))
    )
    (net (code "3") (name "/ADC1") (class "Default")
      (node (ref "U1") (pin "23") (pinfunction "PA1_23") (pintype "bidirectional"))
      (node (ref "X2") (pin "5") (pinfunction "S_5") (pintype "passive"))
    )
    (net (code "4") (name "/ADC1_S") (class "Default")
      (node (ref "R18") (pin "1") (pinfunction "1_1") (pintype "passive"))
      (node (ref "U$11") (pin "P$2") (pinfunction "C_P$2") (pintype "bidirectional"))
      (node (ref "X3") (pin "14") (pinfunction "S_14") (pintype "passive"))
    )
    (net (code "5") (name "/ADC2") (class "Default")
      (node (ref "U1") (pin "24") (pinfunction "PA2_24") (pintype "bidirectional"))
      (node (ref "X2") (pin "6") (pinfunction "S_6") (pintype "passive"))
    )
    (net (code "6") (name "/ADC2_S") (class "Default")
      (node (ref "R20") (pin "1") (pinfunction "1_1") (pintype "passive"))
      (node (ref "U$14") (pin "P$2") (pinfunction "C_P$2") (pintype "bidirectional"))
      (node (ref "X3") (pin "13") (pinfunction "S_13") (pintype "passive"))
    )
    (net (code "7") (name "/ADC3") (class "Default")
      (node (ref "U1") (pin "25") (pinfunction "PA3_25") (pintype "bidirectional"))
      (node (ref "X2") (pin "7") (pinfunction "S_7") (pintype "passive"))
    )
    (net (code "8") (name "/ADC3_S") (class "Default")
      (node (ref "R22") (pin "1") (pinfunction "1_1") (pintype "passive"))
      (node (ref "U$15") (pin "P$2") (pinfunction "C_P$2") (pintype "bidirectional"))
      (node (ref "X3") (pin "12") (pinfunction "S_12") (pintype "passive"))
    )
    (net (code "9") (name "/ADC4") (class "Default")
      (node (ref "U1") (pin "28") (pinfunction "PA4_28") (pintype "bidirectional"))
      (node (ref "X2") (pin "8") (pinfunction "S_8") (pintype "passive"))
    )
    (net (code "10") (name "/ADC4_S") (class "Default")
      (node (ref "R24") (pin "1") (pinfunction "1_1") (pintype "passive"))
      (node (ref "U$16") (pin "P$2") (pinfunction "C_P$2") (pintype "bidirectional"))
      (node (ref "X3") (pin "11") (pinfunction "S_11") (pintype "passive"))
    )
    (net (code "11") (name "/ADC5") (class "Default")
      (node (ref "U1") (pin "29") (pinfunction "PA5_29") (pintype "bidirectional"))
      (node (ref "X2") (pin "9") (pinfunction "S_9") (pintype "passive"))
    )
    (net (code "12") (name "/ADC6") (class "Default")
      (node (ref "U1") (pin "30") (pinfunction "PA6_30") (pintype "bidirectional"))
      (node (ref "X2") (pin "10") (pinfunction "S_10") (pintype "passive"))
    )
    (net (code "13") (name "/ADC6_S") (class "Default")
      (node (ref "R26") (pin "1") (pinfunction "1_1") (pintype "passive"))
      (node (ref "U$17") (pin "P$2") (pinfunction "C_P$2") (pintype "bidirectional"))
      (node (ref "X3") (pin "9") (pinfunction "S_9") (pintype "passive"))
    )
    (net (code "14") (name "/ADC7") (class "Default")
      (node (ref "U1") (pin "31") (pinfunction "PA7_31") (pintype "bidirectional"))
      (node (ref "X2") (pin "11") (pinfunction "S_11") (pintype "passive"))
    )
    (net (code "15") (name "/ADC7_S") (class "Default")
      (node (ref "R28") (pin "1") (pinfunction "1_1") (pintype "passive"))
      (node (ref "U$18") (pin "P$2") (pinfunction "C_P$2") (pintype "bidirectional"))
      (node (ref "X3") (pin "8") (pinfunction "S_8") (pintype "passive"))
    )
    (net (code "16") (name "/ADC8") (class "Default")
      (node (ref "U1") (pin "32") (pinfunction "PC4_32") (pintype "bidirectional"))
      (node (ref "X2") (pin "12") (pinfunction "S_12") (pintype "passive"))
    )
    (net (code "17") (name "/ADC8_S") (class "Default")
      (node (ref "R30") (pin "1") (pinfunction "1_1") (pintype "passive"))
      (node (ref "U$19") (pin "P$2") (pinfunction "C_P$2") (pintype "bidirectional"))
      (node (ref "X3") (pin "7") (pinfunction "S_7") (pintype "passive"))
    )
    (net (code "18") (name "/ADC9") (class "Default")
      (node (ref "U1") (pin "33") (pinfunction "PC5_33") (pintype "bidirectional"))
      (node (ref "X2") (pin "13") (pinfunction "S_13") (pintype "passive"))
    )
    (net (code "19") (name "/ADC9_S") (class "Default")
      (node (ref "R32") (pin "1") (pinfunction "1_1") (pintype "passive"))
      (node (ref "U$20") (pin "P$2") (pinfunction "C_P$2") (pintype "bidirectional"))
      (node (ref "X3") (pin "6") (pinfunction "S_6") (pintype "passive"))
    )
    (net (code "20") (name "/ADC10") (class "Default")
      (node (ref "U1") (pin "34") (pinfunction "PB0_34") (pintype "bidirectional"))
      (node (ref "X2") (pin "14") (pinfunction "S_14") (pintype "passive"))
    )
    (net (code "21") (name "/ADC11") (class "Default")
      (node (ref "CAMERA") (pin "3") (pinfunction "3_3") (pintype "passive"))
      (node (ref "U1") (pin "35") (pinfunction "PB1_35") (pintype "bidirectional"))
    )
    (net (code "22") (name "/BOOT") (class "Default")
      (node (ref "BOOT") (pin "1") (pinfunction "1_1") (pintype "passive"))
      (node (ref "R2") (pin "2") (pinfunction "2_2") (pintype "passive"))
      (node (ref "U1") (pin "94") (pinfunction "BOOT0_94") (pintype "input"))
    )
    (net (code "23") (name "/CAM_CLK") (class "Default")
      (node (ref "CAMERA") (pin "5") (pinfunction "5_5") (pintype "passive"))
      (node (ref "U1") (pin "39") (pinfunction "PE9_39") (pintype "bidirectional"))
    )
    (net (code "24") (name "/CAM_SI") (class "Default")
      (node (ref "CAMERA") (pin "6") (pinfunction "6_6") (pintype "passive"))
      (node (ref "U1") (pin "38") (pinfunction "PE8_38") (pintype "bidirectional"))
    )
    (net (code "25") (name "/ENC_LEFT_SCL") (class "Default")
      (node (ref "R17") (pin "1") (pinfunction "1_1") (pintype "passive"))
      (node (ref "U1") (pin "63") (pinfunction "PC6_63") (pintype "bidirectional"))
      (node (ref "U3") (pin "1") (pinfunction "SCL/SPC_1") (pintype "bidirectional"))
    )
    (net (code "26") (name "/ENC_LEFT_SDA") (class "Default")
      (node (ref "R40") (pin "1") (pinfunction "1_1") (pintype "passive"))
      (node (ref "U1") (pin "64") (pinfunction "PC7_64") (pintype "bidirectional"))
      (node (ref "U3") (pin "4") (pinfunction "SDA/SDI/SDO_4") (pintype "bidirectional"))
    )
    (net (code "27") (name "/ENC_RIGHT_SCL") (class "Default")
      (node (ref "R41") (pin "1") (pinfunction "1_1") (pintype "passive"))
      (node (ref "U1") (pin "90") (pinfunction "PB4_90") (pintype "bidirectional"))
      (node (ref "U4") (pin "1") (pinfunction "SCL/SPC_1") (pintype "bidirectional"))
    )
    (net (code "28") (name "/ENC_RIGHT_SDA") (class "Default")
      (node (ref "R42") (pin "1") (pinfunction "1_1") (pintype "passive"))
      (node (ref "U1") (pin "91") (pinfunction "PB5_91") (pintype "bidirectional"))
      (node (ref "U4") (pin "4") (pinfunction "SDA/SDI/SDO_4") (pintype "bidirectional"))
    )
    (net (code "29") (name "/FRONT_GPIO") (class "Default")
      (node (ref "U1") (pin "17") (pinfunction "PC2_17") (pintype "bidirectional"))
      (node (ref "X2") (pin "3") (pinfunction "S_3") (pintype "passive"))
    )
    (net (code "30") (name "/FRONT_SCL") (class "Default")
      (node (ref "U1") (pin "15") (pinfunction "PC0_15") (pintype "bidirectional"))
      (node (ref "X2") (pin "1") (pinfunction "S_1") (pintype "passive"))
    )
    (net (code "31") (name "/FRONT_SDA") (class "Default")
      (node (ref "U1") (pin "16") (pinfunction "PC1_16") (pintype "bidirectional"))
      (node (ref "X2") (pin "2") (pinfunction "S_2") (pintype "passive"))
    )
    (net (code "32") (name "/IR_A") (class "Default")
      (node (ref "Q2") (pin "3") (pinfunction "D_3") (pintype "passive"))
      (node (ref "X2") (pin "15") (pinfunction "S_15") (pintype "passive"))
    )
    (net (code "33") (name "/IR_A_CONTROLL") (class "Default")
      (node (ref "Q2") (pin "1") (pinfunction "G_1") (pintype "passive"))
      (node (ref "R10") (pin "2") (pinfunction "2_2") (pintype "passive"))
      (node (ref "U1") (pin "37") (pinfunction "PE7_37") (pintype "bidirectional"))
    )
    (net (code "34") (name "/IR_A_S") (class "Default")
      (node (ref "R19") (pin "1") (pinfunction "1_1") (pintype "passive"))
      (node (ref "R21") (pin "1") (pinfunction "1_1") (pintype "passive"))
      (node (ref "R23") (pin "1") (pinfunction "1_1") (pintype "passive"))
      (node (ref "R25") (pin "1") (pinfunction "1_1") (pintype "passive"))
      (node (ref "R27") (pin "1") (pinfunction "1_1") (pintype "passive"))
      (node (ref "R29") (pin "1") (pinfunction "1_1") (pintype "passive"))
      (node (ref "R31") (pin "1") (pinfunction "1_1") (pintype "passive"))
      (node (ref "R33") (pin "1") (pinfunction "1_1") (pintype "passive"))
      (node (ref "X3") (pin "4") (pinfunction "S_4") (pintype "passive"))
    )
    (net (code "35") (name "/IR_B") (class "Default")
      (node (ref "Q3") (pin "3") (pinfunction "D_3") (pintype "passive"))
      (node (ref "X2") (pin "16") (pinfunction "S_16") (pintype "passive"))
    )
    (net (code "36") (name "/IR_B_CONTROLL") (class "Default")
      (node (ref "Q3") (pin "1") (pinfunction "G_1") (pintype "passive"))
      (node (ref "R11") (pin "2") (pinfunction "2_2") (pintype "passive"))
      (node (ref "U1") (pin "36") (pinfunction "PB2_36") (pintype "bidirectional"))
    )
    (net (code "37") (name "/IR_B_S") (class "Default")
      (node (ref "U$13") (pin "P$1_COL") (pinfunction "C_P$1_COL") (pintype "passive"))
      (node (ref "U$30") (pin "P$1_COL") (pinfunction "C_P$1_COL") (pintype "passive"))
      (node (ref "U$32") (pin "P$1_COL") (pinfunction "C_P$1_COL") (pintype "passive"))
      (node (ref "X3") (pin "3") (pinfunction "S_3") (pintype "passive"))
    )
    (net (code "38") (name "/IR_FRONT_S") (class "Default")
      (node (ref "R36") (pin "1") (pinfunction "1_1") (pintype "passive"))
      (node (ref "U$29") (pin "P$1_COL") (pinfunction "P$1_P$1_COL") (pintype "bidirectional"))
      (node (ref "X3") (pin "10") (pinfunction "S_10") (pintype "passive"))
    )
    (net (code "39") (name "/IR_LEFT_S") (class "Default")
      (node (ref "R38") (pin "1") (pinfunction "1_1") (pintype "passive"))
      (node (ref "U$31") (pin "P$1_COL") (pinfunction "P$1_P$1_COL") (pintype "bidirectional"))
      (node (ref "X3") (pin "5") (pinfunction "S_5") (pintype "passive"))
    )
    (net (code "40") (name "/IR_REMOTE") (class "Default")
      (node (ref "J1") (pin "1") (pinfunction "1_1") (pintype "passive"))
      (node (ref "U1") (pin "1") (pinfunction "PE2_1") (pintype "bidirectional"))
    )
    (net (code "41") (name "/IR_RIGHT_S") (class "Default")
      (node (ref "R34") (pin "1") (pinfunction "1_1") (pintype "passive"))
      (node (ref "U$12") (pin "P$1_COL") (pinfunction "P$1_P$1_COL") (pintype "bidirectional"))
      (node (ref "X3") (pin "15") (pinfunction "S_15") (pintype "passive"))
    )
    (net (code "42") (name "/KEY") (class "Default")
      (node (ref "RUN") (pin "3") (pinfunction "3_3") (pintype "passive"))
      (node (ref "U1") (pin "2") (pinfunction "PE3_2") (pintype "bidirectional"))
    )
    (net (code "43") (name "/LED") (class "Default")
      (node (ref "R3") (pin "2") (pinfunction "2_2") (pintype "passive"))
      (node (ref "U1") (pin "67") (pinfunction "PA8_67") (pintype "bidirectional"))
    )
    (net (code "44") (name "/LED_BACK") (class "Default")
      (node (ref "Q4") (pin "1") (pinfunction "G_1") (pintype "passive"))
      (node (ref "R12") (pin "2") (pinfunction "2_2") (pintype "passive"))
      (node (ref "U1") (pin "60") (pinfunction "PD13_60") (pintype "bidirectional"))
    )
    (net (code "45") (name "/MOTOR_ENABLE") (class "Default")
      (node (ref "IC2") (pin "25") (pinfunction "EN/~{D4}_25") (pintype "input"))
      (node (ref "IC2") (pin "3") (pinfunction "EN/~{D2}_3") (pintype "input"))
      (node (ref "R7") (pin "2") (pinfunction "2_2") (pintype "passive"))
      (node (ref "U1") (pin "81") (pinfunction "PD0_81") (pintype "bidirectional"))
    )
    (net (code "46") (name "/NC") (class "Default")
      (node (ref "CAMERA") (pin "4") (pinfunction "4_4") (pintype "passive"))
    )
    (net (code "47") (name "/PWM_A_LEFT") (class "Default")
      (node (ref "IC2") (pin "43") (pinfunction "IN1_43") (pintype "input"))
      (node (ref "U1") (pin "42") (pinfunction "PE12_42") (pintype "bidirectional"))
    )
    (net (code "48") (name "/PWM_A_RIGHT") (class "Default")
      (node (ref "IC2") (pin "21") (pinfunction "IN3_21") (pintype "input"))
      (node (ref "U1") (pin "40") (pinfunction "PE10_40") (pintype "bidirectional"))
    )
    (net (code "49") (name "/PWM_B_LEFT") (class "Default")
      (node (ref "IC2") (pin "42") (pinfunction "IN2_42") (pintype "input"))
      (node (ref "U1") (pin "43") (pinfunction "PE13_43") (pintype "bidirectional"))
    )
    (net (code "50") (name "/PWM_B_RIGHT") (class "Default")
      (node (ref "IC2") (pin "20") (pinfunction "IN4_20") (pintype "input"))
      (node (ref "U1") (pin "41") (pinfunction "PE11_41") (pintype "bidirectional"))
    )
    (net (code "51") (name "/RESET") (class "Default")
      (node (ref "C3") (pin "1") (pinfunction "1_1") (pintype "passive"))
      (node (ref "R1") (pin "1") (pinfunction "1_1") (pintype "passive"))
      (node (ref "RESET") (pin "3") (pinfunction "3_3") (pintype "passive"))
      (node (ref "U1") (pin "14") (pinfunction "NRST_14") (pintype "bidirectional"))
    )
    (net (code "52") (name "/SCL") (class "Default")
      (node (ref "R5") (pin "1") (pinfunction "1_1") (pintype "passive"))
      (node (ref "U$2") (pin "P$2") (pinfunction "SCL/SPC_P$2") (pintype "bidirectional"))
      (node (ref "U1") (pin "83") (pinfunction "PD2_83") (pintype "bidirectional"))
      (node (ref "U2") (pin "6") (pinfunction "SCL_6") (pintype "bidirectional"))
    )
    (net (code "53") (name "/SDA") (class "Default")
      (node (ref "R4") (pin "1") (pinfunction "1_1") (pintype "passive"))
      (node (ref "U$2") (pin "P$3") (pinfunction "SDA/SDI_P$3") (pintype "bidirectional"))
      (node (ref "U1") (pin "82") (pinfunction "PD1_82") (pintype "bidirectional"))
      (node (ref "U2") (pin "5") (pinfunction "SDA_5") (pintype "bidirectional"))
    )
    (net (code "54") (name "/USART1_RX") (class "Default")
      (node (ref "U1") (pin "69") (pinfunction "PA10_69") (pintype "bidirectional"))
      (node (ref "USART") (pin "3") (pinfunction "3_3") (pintype "passive"))
    )
    (net (code "55") (name "/USART1_TX") (class "Default")
      (node (ref "U1") (pin "68") (pinfunction "PA9_68") (pintype "bidirectional"))
      (node (ref "USART") (pin "2") (pinfunction "2_2") (pintype "passive"))
    )
    (net (code "56") (name "/USBDM") (class "Default")
      (node (ref "U1") (pin "70") (pinfunction "PA_11_70") (pintype "bidirectional"))
      (node (ref "X4") (pin "2") (pinfunction "2_2") (pintype "passive"))
    )
    (net (code "57") (name "/USBDP") (class "Default")
      (node (ref "U1") (pin "71") (pinfunction "PA12_71") (pintype "bidirectional"))
      (node (ref "X4") (pin "3") (pinfunction "3_3") (pintype "passive"))
    )
    (net (code "58") (name "/VBAT") (class "Default")
      (node (ref "U1") (pin "6") (pinfunction "VBAT_6") (pintype "power_in"))
    )
    (net (code "59") (name "GND") (class "Default")
      (node (ref "BAT") (pin "1") (pinfunction "1_1") (pintype "passive"))
      (node (ref "C1") (pin "2") (pinfunction "2_2") (pintype "passive"))
      (node (ref "C10") (pin "2") (pinfunction "2_2") (pintype "passive"))
      (node (ref "C11") (pin "2") (pinfunction "2_2") (pintype "passive"))
      (node (ref "C12") (pin "2") (pinfunction "2_2") (pintype "passive"))
      (node (ref "C13") (pin "2") (pinfunction "2_2") (pintype "passive"))
      (node (ref "C14") (pin "2") (pinfunction "2_2") (pintype "passive"))
      (node (ref "C15") (pin "2") (pinfunction "2_2") (pintype "passive"))
      (node (ref "C16") (pin "2") (pinfunction "2_2") (pintype "passive"))
      (node (ref "C19") (pin "2") (pinfunction "2_2") (pintype "passive"))
      (node (ref "C2") (pin "2") (pinfunction "2_2") (pintype "passive"))
      (node (ref "C20") (pin "-") (pinfunction "-_-") (pintype "passive"))
      (node (ref "C21") (pin "-") (pinfunction "-_-") (pintype "passive"))
      (node (ref "C22") (pin "-") (pinfunction "-_-") (pintype "passive"))
      (node (ref "C23") (pin "2") (pinfunction "2_2") (pintype "passive"))
      (node (ref "C24") (pin "-") (pinfunction "-_-") (pintype "passive"))
      (node (ref "C25") (pin "2") (pinfunction "2_2") (pintype "passive"))
      (node (ref "C26") (pin "2") (pinfunction "2_2") (pintype "passive"))
      (node (ref "C27") (pin "2") (pinfunction "2_2") (pintype "passive"))
      (node (ref "C28") (pin "2") (pinfunction "2_2") (pintype "passive"))
      (node (ref "C29") (pin "2") (pinfunction "2_2") (pintype "passive"))
      (node (ref "C3") (pin "2") (pinfunction "2_2") (pintype "passive"))
      (node (ref "C4") (pin "2") (pinfunction "2_2") (pintype "passive"))
      (node (ref "C5") (pin "1") (pinfunction "1_1") (pintype "passive"))
      (node (ref "C6") (pin "2") (pinfunction "2_2") (pintype "passive"))
      (node (ref "C7") (pin "2") (pinfunction "2_2") (pintype "passive"))
      (node (ref "C8") (pin "2") (pinfunction "2_2") (pintype "passive"))
      (node (ref "C9") (pin "2") (pinfunction "2_2") (pintype "passive"))
      (node (ref "CAMERA") (pin "2") (pinfunction "2_2") (pintype "passive"))
      (node (ref "IC1") (pin "2") (pinfunction "GND_2") (pintype "passive"))
      (node (ref "IC2") (pin "1") (pinfunction "D1_1") (pintype "input"))
      (node (ref "IC2") (pin "10") (pinfunction "PGNDA_10") (pintype "power_in"))
      (node (ref "IC2") (pin "11") (pinfunction "PGNDA_11") (pintype "power_in"))
      (node (ref "IC2") (pin "12") (pinfunction "PGNDB_12") (pintype "power_in"))
      (node (ref "IC2") (pin "13") (pinfunction "PGNDB_13") (pintype "power_in"))
      (node (ref "IC2") (pin "23") (pinfunction "D3_23") (pintype "input"))
      (node (ref "IC2") (pin "32") (pinfunction "PGNDB_32") (pintype "power_in"))
      (node (ref "IC2") (pin "33") (pinfunction "PGNDB_33") (pintype "power_in"))
      (node (ref "IC2") (pin "34") (pinfunction "PGNDA_34") (pintype "power_in"))
      (node (ref "IC2") (pin "35") (pinfunction "PGNDA_35") (pintype "power_in"))
      (node (ref "IC2") (pin "EH@1") (pinfunction "EH_EH@1") (pintype "passive"))
      (node (ref "IC2") (pin "EH@2") (pinfunction "EH_EH@2") (pintype "passive"))
      (node (ref "IC2") (pin "EH@3") (pinfunction "EH_EH@3") (pintype "passive"))
      (node (ref "J1") (pin "2") (pinfunction "2_2") (pintype "passive"))
      (node (ref "LED1") (pin "C") (pinfunction "C_C") (pintype "passive"))
      (node (ref "LED2") (pin "C") (pinfunction "C_C") (pintype "passive"))
      (node (ref "Q2") (pin "2") (pinfunction "S_2") (pintype "passive"))
      (node (ref "Q3") (pin "2") (pinfunction "S_2") (pintype "passive"))
      (node (ref "Q4") (pin "2") (pinfunction "S_2") (pintype "passive"))
      (node (ref "R10") (pin "1") (pinfunction "1_1") (pintype "passive"))
      (node (ref "R11") (pin "1") (pinfunction "1_1") (pintype "passive"))
      (node (ref "R12") (pin "1") (pinfunction "1_1") (pintype "passive"))
      (node (ref "R2") (pin "1") (pinfunction "1_1") (pintype "passive"))
      (node (ref "R7") (pin "1") (pinfunction "1_1") (pintype "passive"))
      (node (ref "R8") (pin "1") (pinfunction "1_1") (pintype "passive"))
      (node (ref "R9") (pin "2") (pinfunction "2_2") (pintype "passive"))
      (node (ref "RESET") (pin "1") (pinfunction "1_1") (pintype "passive"))
      (node (ref "RUN") (pin "1") (pinfunction "1_1") (pintype "passive"))
      (node (ref "U$11") (pin "P$1") (pinfunction "E_P$1") (pintype "bidirectional"))
      (node (ref "U$12") (pin "P$2_EM") (pinfunction "P$2_P$2_EM") (pintype "bidirectional"))
      (node (ref "U$12") (pin "P$3-NC") (pinfunction "P$2_P$3-NC") (pintype "bidirectional"))
      (node (ref "U$14") (pin "P$1") (pinfunction "E_P$1") (pintype "bidirectional"))
      (node (ref "U$15") (pin "P$1") (pinfunction "E_P$1") (pintype "bidirectional"))
      (node (ref "U$16") (pin "P$1") (pinfunction "E_P$1") (pintype "bidirectional"))
      (node (ref "U$17") (pin "P$1") (pinfunction "E_P$1") (pintype "bidirectional"))
      (node (ref "U$18") (pin "P$1") (pinfunction "E_P$1") (pintype "bidirectional"))
      (node (ref "U$19") (pin "P$1") (pinfunction "E_P$1") (pintype "bidirectional"))
      (node (ref "U$2") (pin "P$10") (pinfunction "RES2_P$10") (pintype "bidirectional"))
      (node (ref "U$2") (pin "P$11") (pinfunction "RES3_P$11") (pintype "bidirectional"))
      (node (ref "U$2") (pin "P$12") (pinfunction "GND_P$12") (pintype "power_in"))
      (node (ref "U$2") (pin "P$13") (pinfunction "GND_P$13") (pintype "power_in"))
      (node (ref "U$2") (pin "P$15") (pinfunction "RES4_P$15") (pintype "bidirectional"))
      (node (ref "U$2") (pin "P$4") (pinfunction "SDO_P$4") (pintype "bidirectional"))
      (node (ref "U$2") (pin "P$8") (pinfunction "DEN_P$8") (pintype "bidirectional"))
      (node (ref "U$2") (pin "P$9") (pinfunction "RES1_P$9") (pintype "bidirectional"))
      (node (ref "U$20") (pin "P$1") (pinfunction "E_P$1") (pintype "bidirectional"))
      (node (ref "U$29") (pin "P$2_EM") (pinfunction "P$2_P$2_EM") (pintype "bidirectional"))
      (node (ref "U$29") (pin "P$3-NC") (pinfunction "P$2_P$3-NC") (pintype "bidirectional"))
      (node (ref "U$31") (pin "P$2_EM") (pinfunction "P$2_P$2_EM") (pintype "bidirectional"))
      (node (ref "U$31") (pin "P$3-NC") (pinfunction "P$2_P$3-NC") (pintype "bidirectional"))
      (node (ref "U1") (pin "10") (pinfunction "VSS_2_10") (pintype "passive"))
      (node (ref "U1") (pin "19") (pinfunction "VSSA_19") (pintype "passive"))
      (node (ref "U1") (pin "26") (pinfunction "VSS_26") (pintype "passive"))
      (node (ref "U1") (pin "49") (pinfunction "VSS_4_49") (pintype "power_in"))
      (node (ref "U1") (pin "74") (pinfunction "VSS_2_74") (pintype "passive"))
      (node (ref "U1") (pin "99") (pinfunction "VSS_99") (pintype "passive"))
      (node (ref "U2") (pin "1") (pinfunction "A0_1") (pintype "bidirectional"))
      (node (ref "U2") (pin "2") (pinfunction "A1_2") (pintype "bidirectional"))
      (node (ref "U2") (pin "3") (pinfunction "A2_3") (pintype "bidirectional"))
      (node (ref "U2") (pin "4") (pinfunction "VSS_4") (pintype "power_in"))
      (node (ref "U3") (pin "6") (pinfunction "GND_6") (pintype "bidirectional"))
      (node (ref "U3") (pin "8") (pinfunction "GND_8") (pintype "bidirectional"))
      (node (ref "U4") (pin "6") (pinfunction "GND_6") (pintype "bidirectional"))
      (node (ref "U4") (pin "8") (pinfunction "GND_8") (pintype "bidirectional"))
      (node (ref "USART") (pin "1") (pinfunction "1_1") (pintype "passive"))
      (node (ref "X2") (pin "18") (pinfunction "S_18") (pintype "passive"))
      (node (ref "X3") (pin "1") (pinfunction "S_1") (pintype "passive"))
      (node (ref "X4") (pin "5") (pinfunction "5_5") (pintype "passive"))
      (node (ref "X4") (pin "M1") (pinfunction "S1_M1") (pintype "passive"))
      (node (ref "X4") (pin "M2") (pinfunction "S2_M2") (pintype "passive"))
      (node (ref "X4") (pin "M3") (pinfunction "S3_M3") (pintype "passive"))
      (node (ref "X4") (pin "M4") (pinfunction "S4_M4") (pintype "passive"))
    )
    (net (code "60") (name "Net-(D1-PadA)") (class "Default")
      (node (ref "D1") (pin "A") (pinfunction "A_A") (pintype "passive"))
      (node (ref "X4") (pin "1") (pinfunction "1_1") (pintype "passive"))
    )
    (net (code "61") (name "Net-(IC2-CCPA)") (class "Default")
      (node (ref "C17") (pin "2") (pinfunction "2_2") (pintype "passive"))
      (node (ref "IC2") (pin "41") (pinfunction "CCPA_41") (pintype "output"))
    )
    (net (code "62") (name "Net-(IC2-CCPB)") (class "Default")
      (node (ref "C18") (pin "1") (pinfunction "1_1") (pintype "passive"))
      (node (ref "IC2") (pin "19") (pinfunction "CCPB_19") (pintype "output"))
    )
    (net (code "63") (name "Net-(IC2-FBA)") (class "Default")
      (node (ref "IC2") (pin "2") (pinfunction "FBA_2") (pintype "output"))
      (node (ref "R8") (pin "2") (pinfunction "2_2") (pintype "passive"))
    )
    (net (code "64") (name "Net-(IC2-FBB)") (class "Default")
      (node (ref "IC2") (pin "24") (pinfunction "FBB_24") (pintype "output"))
      (node (ref "R9") (pin "1") (pinfunction "1_1") (pintype "passive"))
    )
    (net (code "65") (name "Net-(IC2-OUT1-Pad7)") (class "Default")
      (node (ref "IC2") (pin "7") (pinfunction "OUT1_7") (pintype "output"))
      (node (ref "IC2") (pin "8") (pinfunction "OUT1_8") (pintype "passive"))
      (node (ref "IC2") (pin "9") (pinfunction "OUT1_9") (pintype "passive"))
      (node (ref "U$26") (pin "P$2") (pinfunction "P$2_P$2") (pintype "bidirectional"))
    )
    (net (code "66") (name "Net-(IC2-OUT2-Pad36)") (class "Default")
      (node (ref "IC2") (pin "36") (pinfunction "OUT2_36") (pintype "output"))
      (node (ref "IC2") (pin "37") (pinfunction "OUT2_37") (pintype "passive"))
      (node (ref "IC2") (pin "38") (pinfunction "OUT2_38") (pintype "passive"))
      (node (ref "U$26") (pin "P$1") (pinfunction "P$1_P$1") (pintype "bidirectional"))
    )
    (net (code "67") (name "Net-(IC2-OUT3-Pad29)") (class "Default")
      (node (ref "IC2") (pin "29") (pinfunction "OUT3_29") (pintype "output"))
      (node (ref "IC2") (pin "30") (pinfunction "OUT3_30") (pintype "passive"))
      (node (ref "IC2") (pin "31") (pinfunction "OUT3_31") (pintype "passive"))
      (node (ref "U$27") (pin "P$2") (pinfunction "P$2_P$2") (pintype "bidirectional"))
    )
    (net (code "68") (name "Net-(IC2-OUT4-Pad14)") (class "Default")
      (node (ref "IC2") (pin "14") (pinfunction "OUT4_14") (pintype "output"))
      (node (ref "IC2") (pin "15") (pinfunction "OUT4_15") (pintype "passive"))
      (node (ref "IC2") (pin "16") (pinfunction "OUT4_16") (pintype "passive"))
      (node (ref "U$27") (pin "P$1") (pinfunction "P$1_P$1") (pintype "bidirectional"))
    )
    (net (code "69") (name "Net-(LED1-PadA)") (class "Default")
      (node (ref "LED1") (pin "A") (pinfunction "A_A") (pintype "passive"))
      (node (ref "R3") (pin "1") (pinfunction "1_1") (pintype "passive"))
    )
    (net (code "70") (name "Net-(LED2-PadA)") (class "Default")
      (node (ref "LED2") (pin "A") (pinfunction "A_A") (pintype "passive"))
      (node (ref "R6") (pin "1") (pinfunction "1_1") (pintype "passive"))
    )
    (net (code "71") (name "Net-(LED3-PadA)") (class "Default")
      (node (ref "LED3") (pin "A") (pinfunction "A_A") (pintype "passive"))
      (node (ref "R13") (pin "1") (pinfunction "1_1") (pintype "passive"))
    )
    (net (code "72") (name "Net-(LED4-PadA)") (class "Default")
      (node (ref "LED4") (pin "A") (pinfunction "A_A") (pintype "passive"))
      (node (ref "R14") (pin "1") (pinfunction "1_1") (pintype "passive"))
    )
    (net (code "73") (name "Net-(LED5-PadA)") (class "Default")
      (node (ref "LED5") (pin "A") (pinfunction "A_A") (pintype "passive"))
      (node (ref "R15") (pin "1") (pinfunction "1_1") (pintype "passive"))
    )
    (net (code "74") (name "Net-(LED6-PadA)") (class "Default")
      (node (ref "LED6") (pin "A") (pinfunction "A_A") (pintype "passive"))
      (node (ref "R16") (pin "1") (pinfunction "1_1") (pintype "passive"))
    )
    (net (code "75") (name "Net-(LED7-PadC)") (class "Default")
      (node (ref "LED7") (pin "C") (pinfunction "C_C") (pintype "passive"))
      (node (ref "R19") (pin "2") (pinfunction "2_2") (pintype "passive"))
    )
    (net (code "76") (name "Net-(LED8-PadC)") (class "Default")
      (node (ref "LED8") (pin "C") (pinfunction "C_C") (pintype "passive"))
      (node (ref "R21") (pin "2") (pinfunction "2_2") (pintype "passive"))
    )
    (net (code "77") (name "Net-(LED9-PadC)") (class "Default")
      (node (ref "LED9") (pin "C") (pinfunction "C_C") (pintype "passive"))
      (node (ref "R23") (pin "2") (pinfunction "2_2") (pintype "passive"))
    )
    (net (code "78") (name "Net-(LED10-PadC)") (class "Default")
      (node (ref "LED10") (pin "C") (pinfunction "C_C") (pintype "passive"))
      (node (ref "R25") (pin "2") (pinfunction "2_2") (pintype "passive"))
    )
    (net (code "79") (name "Net-(LED11-PadC)") (class "Default")
      (node (ref "LED11") (pin "C") (pinfunction "C_C") (pintype "passive"))
      (node (ref "R27") (pin "2") (pinfunction "2_2") (pintype "passive"))
    )
    (net (code "80") (name "Net-(LED12-PadC)") (class "Default")
      (node (ref "LED12") (pin "C") (pinfunction "C_C") (pintype "passive"))
      (node (ref "R29") (pin "2") (pinfunction "2_2") (pintype "passive"))
    )
    (net (code "81") (name "Net-(LED13-PadC)") (class "Default")
      (node (ref "LED13") (pin "C") (pinfunction "C_C") (pintype "passive"))
      (node (ref "R31") (pin "2") (pinfunction "2_2") (pintype "passive"))
    )
    (net (code "82") (name "Net-(LED14-PadC)") (class "Default")
      (node (ref "LED14") (pin "C") (pinfunction "C_C") (pintype "passive"))
      (node (ref "R33") (pin "2") (pinfunction "2_2") (pintype "passive"))
    )
    (net (code "83") (name "Net-(Q1-2)") (class "Default")
      (node (ref "C2") (pin "1") (pinfunction "1_1") (pintype "passive"))
      (node (ref "Q1") (pin "3") (pinfunction "2_3") (pintype "passive"))
      (node (ref "U1") (pin "12") (pinfunction "PH0_12") (pintype "bidirectional"))
    )
    (net (code "84") (name "Net-(Q4-D)") (class "Default")
      (node (ref "LED3") (pin "C") (pinfunction "C_C") (pintype "passive"))
      (node (ref "LED4") (pin "C") (pinfunction "C_C") (pintype "passive"))
      (node (ref "LED5") (pin "C") (pinfunction "C_C") (pintype "passive"))
      (node (ref "LED6") (pin "C") (pinfunction "C_C") (pintype "passive"))
      (node (ref "Q4") (pin "3") (pinfunction "D_3") (pintype "passive"))
    )
    (net (code "85") (name "Net-(R35-Pad1)") (class "Default")
      (node (ref "R35") (pin "1") (pinfunction "1_1") (pintype "passive"))
      (node (ref "U$13") (pin "P$2_EM") (pinfunction "A_P$2_EM") (pintype "passive"))
      (node (ref "U$13") (pin "P$3-NC") (pinfunction "A_P$3-NC") (pintype "passive"))
    )
    (net (code "86") (name "Net-(R37-Pad1)") (class "Default")
      (node (ref "R37") (pin "1") (pinfunction "1_1") (pintype "passive"))
      (node (ref "U$30") (pin "P$2_EM") (pinfunction "A_P$2_EM") (pintype "passive"))
      (node (ref "U$30") (pin "P$3-NC") (pinfunction "A_P$3-NC") (pintype "passive"))
    )
    (net (code "87") (name "Net-(R39-Pad1)") (class "Default")
      (node (ref "R39") (pin "1") (pinfunction "1_1") (pintype "passive"))
      (node (ref "U$32") (pin "P$2_EM") (pinfunction "A_P$2_EM") (pintype "passive"))
      (node (ref "U$32") (pin "P$3-NC") (pinfunction "A_P$3-NC") (pintype "passive"))
    )
    (net (code "88") (name "Net-(U$2-CAP)") (class "Default")
      (node (ref "C14") (pin "1") (pinfunction "1_1") (pintype "passive"))
      (node (ref "U$2") (pin "P$14") (pinfunction "CAP_P$14") (pintype "bidirectional"))
    )
    (net (code "89") (name "Net-(U1A-PH1)") (class "Default")
      (node (ref "C1") (pin "1") (pinfunction "1_1") (pintype "passive"))
      (node (ref "Q1") (pin "1") (pinfunction "1_1") (pintype "passive"))
      (node (ref "U1") (pin "13") (pinfunction "PH1_13") (pintype "bidirectional"))
    )
    (net (code "90") (name "Net-(U1A-VCAP_1)") (class "Default")
      (node (ref "C4") (pin "1") (pinfunction "1_1") (pintype "passive"))
      (node (ref "U1") (pin "48") (pinfunction "VCAP_1_48") (pintype "power_in"))
    )
    (net (code "91") (name "Net-(U1B-VCAP_2)") (class "Default")
      (node (ref "C5") (pin "2") (pinfunction "2_2") (pintype "passive"))
      (node (ref "U1") (pin "73") (pinfunction "VCAP_2_73") (pintype "power_in"))
    )
    (net (code "92") (name "Net-(U3-C1)") (class "Default")
      (node (ref "C25") (pin "1") (pinfunction "1_1") (pintype "passive"))
      (node (ref "U3") (pin "5") (pinfunction "C1_5") (pintype "bidirectional"))
    )
    (net (code "93") (name "Net-(U4-C1)") (class "Default")
      (node (ref "C28") (pin "1") (pinfunction "1_1") (pintype "passive"))
      (node (ref "U4") (pin "5") (pinfunction "C1_5") (pintype "bidirectional"))
    )
    (net (code "94") (name "VCC") (class "Default")
      (node (ref "BAT") (pin "2") (pinfunction "2_2") (pintype "passive"))
      (node (ref "C10") (pin "1") (pinfunction "1_1") (pintype "passive"))
      (node (ref "C11") (pin "1") (pinfunction "1_1") (pintype "passive"))
      (node (ref "C17") (pin "1") (pinfunction "1_1") (pintype "passive"))
      (node (ref "C18") (pin "2") (pinfunction "2_2") (pintype "passive"))
      (node (ref "C19") (pin "1") (pinfunction "1_1") (pintype "passive"))
      (node (ref "C20") (pin "+") (pinfunction "+_+") (pintype "passive"))
      (node (ref "C21") (pin "+") (pinfunction "+_+") (pintype "passive"))
      (node (ref "C23") (pin "1") (pinfunction "1_1") (pintype "passive"))
      (node (ref "D1") (pin "C") (pinfunction "C_C") (pintype "passive"))
      (node (ref "IC1") (pin "1") (pinfunction "VI_1") (pintype "input"))
      (node (ref "IC2") (pin "17") (pinfunction "VPWRB_17") (pintype "input"))
      (node (ref "IC2") (pin "18") (pinfunction "VPWRB_18") (pintype "input"))
      (node (ref "IC2") (pin "26") (pinfunction "VPWRB_26") (pintype "input"))
      (node (ref "IC2") (pin "27") (pinfunction "VPWRB_27") (pintype "input"))
      (node (ref "IC2") (pin "28") (pinfunction "VPWRB_28") (pintype "input"))
      (node (ref "IC2") (pin "39") (pinfunction "VPWRA_39") (pintype "input"))
      (node (ref "IC2") (pin "4") (pinfunction "VPWRA_4") (pintype "input"))
      (node (ref "IC2") (pin "40") (pinfunction "VPWRA_40") (pintype "input"))
      (node (ref "IC2") (pin "5") (pinfunction "VPWRA_5") (pintype "input"))
      (node (ref "IC2") (pin "6") (pinfunction "VPWRA_6") (pintype "input"))
    )
    (net (code "95") (name "unconnected-(IC2-~{SFA}-Pad44)") (class "Default")
      (node (ref "IC2") (pin "44") (pinfunction "~{SFA}_44") (pintype "open_collector"))
    )
    (net (code "96") (name "unconnected-(IC2-~{SFB}-Pad22)") (class "Default")
      (node (ref "IC2") (pin "22") (pinfunction "~{SFB}_22") (pintype "open_collector"))
    )
    (net (code "97") (name "unconnected-(RESET-Pad2)") (class "Default")
      (node (ref "RESET") (pin "2") (pinfunction "2_2") (pintype "passive"))
    )
    (net (code "98") (name "unconnected-(RESET-Pad4)") (class "Default")
      (node (ref "RESET") (pin "4") (pinfunction "4_4") (pintype "passive"))
    )
    (net (code "99") (name "unconnected-(RUN-Pad2)") (class "Default")
      (node (ref "RUN") (pin "2") (pinfunction "2_2") (pintype "passive"))
    )
    (net (code "100") (name "unconnected-(RUN-Pad4)") (class "Default")
      (node (ref "RUN") (pin "4") (pinfunction "4_4") (pintype "passive"))
    )
    (net (code "101") (name "unconnected-(U$2-DRDY{slash}INT2-PadP$6)") (class "Default")
      (node (ref "U$2") (pin "P$6") (pinfunction "DRDY/INT2_P$6") (pintype "bidirectional"))
    )
    (net (code "102") (name "unconnected-(U$2-INT1-PadP$7)") (class "Default")
      (node (ref "U$2") (pin "P$7") (pinfunction "INT1_P$7") (pintype "bidirectional"))
    )
    (net (code "103") (name "unconnected-(U1A-PB10-Pad46)") (class "Default")
      (node (ref "U1") (pin "46") (pinfunction "PB10_46") (pintype "bidirectional"))
    )
    (net (code "104") (name "unconnected-(U1A-PB11-Pad47)") (class "Default")
      (node (ref "U1") (pin "47") (pinfunction "PB11_47") (pintype "bidirectional"))
    )
    (net (code "105") (name "unconnected-(U1A-PC3-Pad18)") (class "Default")
      (node (ref "U1") (pin "18") (pinfunction "PC3_18") (pintype "bidirectional"))
    )
    (net (code "106") (name "unconnected-(U1A-PC13-Pad7)") (class "Default")
      (node (ref "U1") (pin "7") (pinfunction "PC13_7") (pintype "bidirectional"))
    )
    (net (code "107") (name "unconnected-(U1A-PC14-Pad8)") (class "Default")
      (node (ref "U1") (pin "8") (pinfunction "PC14_8") (pintype "bidirectional"))
    )
    (net (code "108") (name "unconnected-(U1A-PC15-Pad9)") (class "Default")
      (node (ref "U1") (pin "9") (pinfunction "PC15_9") (pintype "bidirectional"))
    )
    (net (code "109") (name "unconnected-(U1A-PE4-Pad3)") (class "Default")
      (node (ref "U1") (pin "3") (pinfunction "PE4_3") (pintype "bidirectional"))
    )
    (net (code "110") (name "unconnected-(U1A-PE5-Pad4)") (class "Default")
      (node (ref "U1") (pin "4") (pinfunction "PE5_4") (pintype "bidirectional"))
    )
    (net (code "111") (name "unconnected-(U1A-PE6-Pad5)") (class "Default")
      (node (ref "U1") (pin "5") (pinfunction "PE6_5") (pintype "bidirectional"))
    )
    (net (code "112") (name "unconnected-(U1A-PE14-Pad44)") (class "Default")
      (node (ref "U1") (pin "44") (pinfunction "PE14_44") (pintype "bidirectional"))
    )
    (net (code "113") (name "unconnected-(U1A-PE15-Pad45)") (class "Default")
      (node (ref "U1") (pin "45") (pinfunction "PE15_45") (pintype "bidirectional"))
    )
    (net (code "114") (name "unconnected-(U1B-PA13-Pad72)") (class "Default")
      (node (ref "U1") (pin "72") (pinfunction "PA13_72") (pintype "bidirectional"))
    )
    (net (code "115") (name "unconnected-(U1B-PA14-Pad76)") (class "Default")
      (node (ref "U1") (pin "76") (pinfunction "PA14_76") (pintype "bidirectional"))
    )
    (net (code "116") (name "unconnected-(U1B-PA15-Pad77)") (class "Default")
      (node (ref "U1") (pin "77") (pinfunction "PA15_77") (pintype "bidirectional"))
    )
    (net (code "117") (name "unconnected-(U1B-PB3-Pad89)") (class "Default")
      (node (ref "U1") (pin "89") (pinfunction "PB3_89") (pintype "bidirectional"))
    )
    (net (code "118") (name "unconnected-(U1B-PB6-Pad92)") (class "Default")
      (node (ref "U1") (pin "92") (pinfunction "PB6_92") (pintype "bidirectional"))
    )
    (net (code "119") (name "unconnected-(U1B-PB7-Pad93)") (class "Default")
      (node (ref "U1") (pin "93") (pinfunction "PB7_93") (pintype "bidirectional"))
    )
    (net (code "120") (name "unconnected-(U1B-PB8-Pad95)") (class "Default")
      (node (ref "U1") (pin "95") (pinfunction "PB8_95") (pintype "bidirectional"))
    )
    (net (code "121") (name "unconnected-(U1B-PB9-Pad96)") (class "Default")
      (node (ref "U1") (pin "96") (pinfunction "PB9_96") (pintype "bidirectional"))
    )
    (net (code "122") (name "unconnected-(U1B-PB12-Pad51)") (class "Default")
      (node (ref "U1") (pin "51") (pinfunction "PB12_51") (pintype "bidirectional"))
    )
    (net (code "123") (name "unconnected-(U1B-PB13-Pad52)") (class "Default")
      (node (ref "U1") (pin "52") (pinfunction "PB13_52") (pintype "bidirectional"))
    )
    (net (code "124") (name "unconnected-(U1B-PB14-Pad53)") (class "Default")
      (node (ref "U1") (pin "53") (pinfunction "PB14_53") (pintype "bidirectional"))
    )
    (net (code "125") (name "unconnected-(U1B-PB15-Pad54)") (class "Default")
      (node (ref "U1") (pin "54") (pinfunction "PB15_54") (pintype "bidirectional"))
    )
    (net (code "126") (name "unconnected-(U1B-PC8-Pad65)") (class "Default")
      (node (ref "U1") (pin "65") (pinfunction "PC8_65") (pintype "bidirectional"))
    )
    (net (code "127") (name "unconnected-(U1B-PC9-Pad66)") (class "Default")
      (node (ref "U1") (pin "66") (pinfunction "PC9_66") (pintype "bidirectional"))
    )
    (net (code "128") (name "unconnected-(U1B-PC10-Pad78)") (class "Default")
      (node (ref "U1") (pin "78") (pinfunction "PC10_78") (pintype "bidirectional"))
    )
    (net (code "129") (name "unconnected-(U1B-PC11-Pad79)") (class "Default")
      (node (ref "U1") (pin "79") (pinfunction "PC11_79") (pintype "bidirectional"))
    )
    (net (code "130") (name "unconnected-(U1B-PC12-Pad80)") (class "Default")
      (node (ref "U1") (pin "80") (pinfunction "PC12_80") (pintype "bidirectional"))
    )
    (net (code "131") (name "unconnected-(U1B-PD3-Pad84)") (class "Default")
      (node (ref "U1") (pin "84") (pinfunction "PD3_84") (pintype "bidirectional"))
    )
    (net (code "132") (name "unconnected-(U1B-PD4-Pad85)") (class "Default")
      (node (ref "U1") (pin "85") (pinfunction "PD4_85") (pintype "bidirectional"))
    )
    (net (code "133") (name "unconnected-(U1B-PD5-Pad86)") (class "Default")
      (node (ref "U1") (pin "86") (pinfunction "PD5_86") (pintype "bidirectional"))
    )
    (net (code "134") (name "unconnected-(U1B-PD6-Pad87)") (class "Default")
      (node (ref "U1") (pin "87") (pinfunction "PD6_87") (pintype "bidirectional"))
    )
    (net (code "135") (name "unconnected-(U1B-PD7-Pad88)") (class "Default")
      (node (ref "U1") (pin "88") (pinfunction "PD7_88") (pintype "bidirectional"))
    )
    (net (code "136") (name "unconnected-(U1B-PD8-Pad55)") (class "Default")
      (node (ref "U1") (pin "55") (pinfunction "PD8_55") (pintype "bidirectional"))
    )
    (net (code "137") (name "unconnected-(U1B-PD9-Pad56)") (class "Default")
      (node (ref "U1") (pin "56") (pinfunction "PD9_56") (pintype "bidirectional"))
    )
    (net (code "138") (name "unconnected-(U1B-PD10-Pad57)") (class "Default")
      (node (ref "U1") (pin "57") (pinfunction "PD10_57") (pintype "bidirectional"))
    )
    (net (code "139") (name "unconnected-(U1B-PD11-Pad58)") (class "Default")
      (node (ref "U1") (pin "58") (pinfunction "PD11_58") (pintype "bidirectional"))
    )
    (net (code "140") (name "unconnected-(U1B-PD12-Pad59)") (class "Default")
      (node (ref "U1") (pin "59") (pinfunction "PD12_59") (pintype "bidirectional"))
    )
    (net (code "141") (name "unconnected-(U1B-PD14-Pad61)") (class "Default")
      (node (ref "U1") (pin "61") (pinfunction "PD14_61") (pintype "bidirectional"))
    )
    (net (code "142") (name "unconnected-(U1B-PD15-Pad62)") (class "Default")
      (node (ref "U1") (pin "62") (pinfunction "PD15_62") (pintype "bidirectional"))
    )
    (net (code "143") (name "unconnected-(U1B-PE0-Pad97)") (class "Default")
      (node (ref "U1") (pin "97") (pinfunction "PE0_97") (pintype "bidirectional"))
    )
    (net (code "144") (name "unconnected-(U1B-PE1-Pad98)") (class "Default")
      (node (ref "U1") (pin "98") (pinfunction "PE1_98") (pintype "bidirectional"))
    )
    (net (code "145") (name "unconnected-(U3-DRDY_MAG-Pad11)") (class "Default")
      (node (ref "U3") (pin "11") (pinfunction "DRDY_MAG_11") (pintype "bidirectional"))
    )
    (net (code "146") (name "unconnected-(U3-INT_MAG-Pad7)") (class "Default")
      (node (ref "U3") (pin "7") (pinfunction "INT_MAG_7") (pintype "bidirectional"))
    )
    (net (code "147") (name "unconnected-(U3-INT_XL-Pad12)") (class "Default")
      (node (ref "U3") (pin "12") (pinfunction "INT_XL_12") (pintype "bidirectional"))
    )
    (net (code "148") (name "unconnected-(U4-DRDY_MAG-Pad11)") (class "Default")
      (node (ref "U4") (pin "11") (pinfunction "DRDY_MAG_11") (pintype "bidirectional"))
    )
    (net (code "149") (name "unconnected-(U4-INT_MAG-Pad7)") (class "Default")
      (node (ref "U4") (pin "7") (pinfunction "INT_MAG_7") (pintype "bidirectional"))
    )
    (net (code "150") (name "unconnected-(U4-INT_XL-Pad12)") (class "Default")
      (node (ref "U4") (pin "12") (pinfunction "INT_XL_12") (pintype "bidirectional"))
    )
    (net (code "151") (name "unconnected-(X3H-S-Pad16)") (class "Default")
      (node (ref "X3") (pin "16") (pinfunction "S_16") (pintype "passive"))
    )
    (net (code "152") (name "unconnected-(X3I-S-Pad17)") (class "Default")
      (node (ref "X3") (pin "17") (pinfunction "S_17") (pintype "passive"))
    )
    (net (code "153") (name "unconnected-(X3J-S-Pad18)") (class "Default")
      (node (ref "X3") (pin "18") (pinfunction "S_18") (pintype "passive"))
    )
    (net (code "154") (name "unconnected-(X4-Pad4)") (class "Default")
      (node (ref "X4") (pin "4") (pinfunction "4_4") (pintype "passive"))
    )
  )
)
